# axiom_beta_sensor_cmv12000_tht_v0_16_r1_.net
KiCad netlist of a schematic drawn in EAGLE
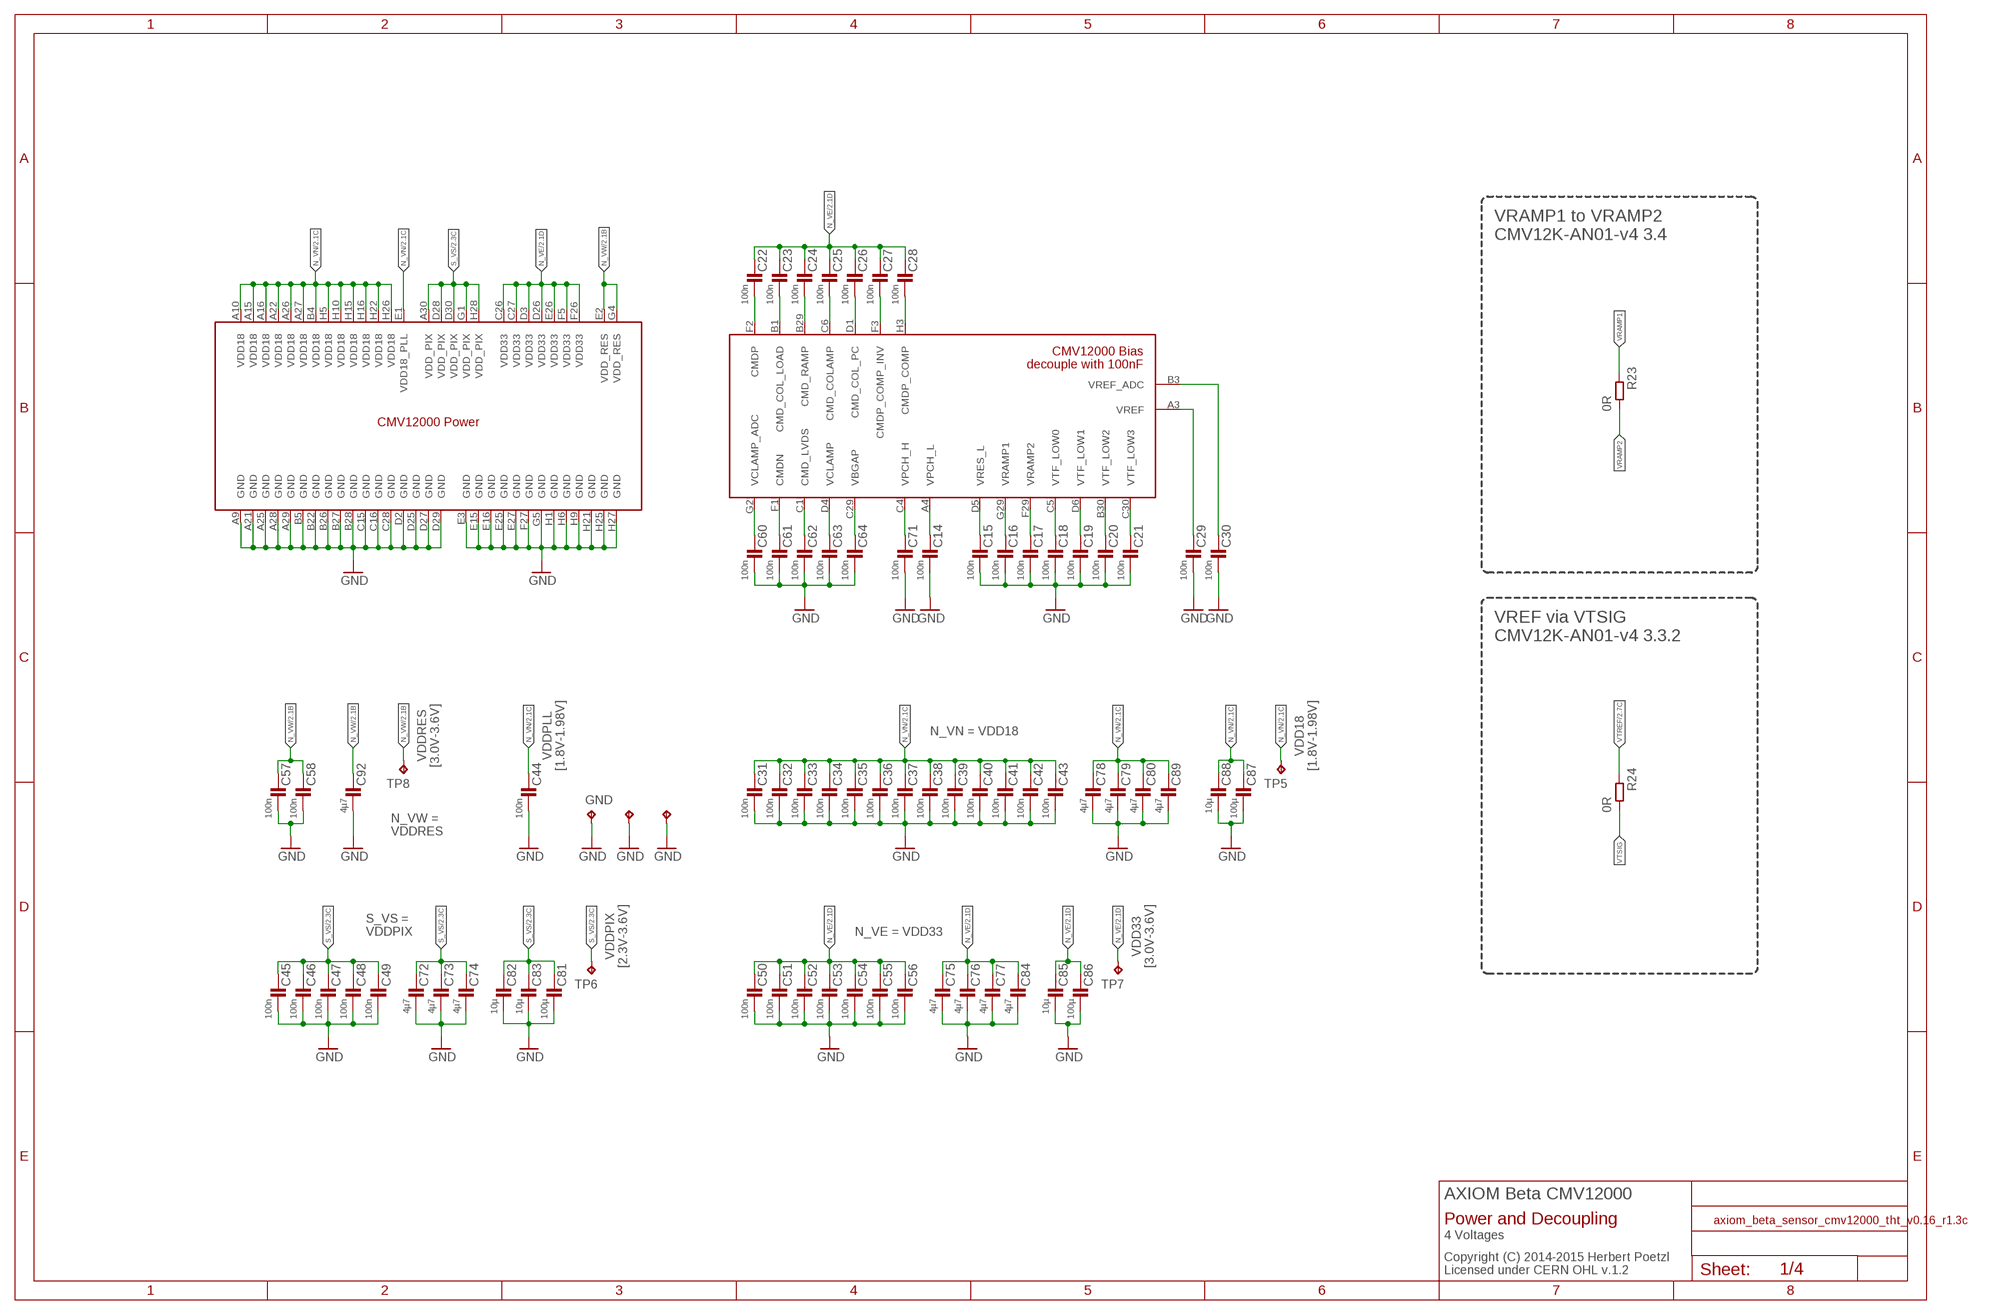
[diagram p0: schematic, sheet 1]
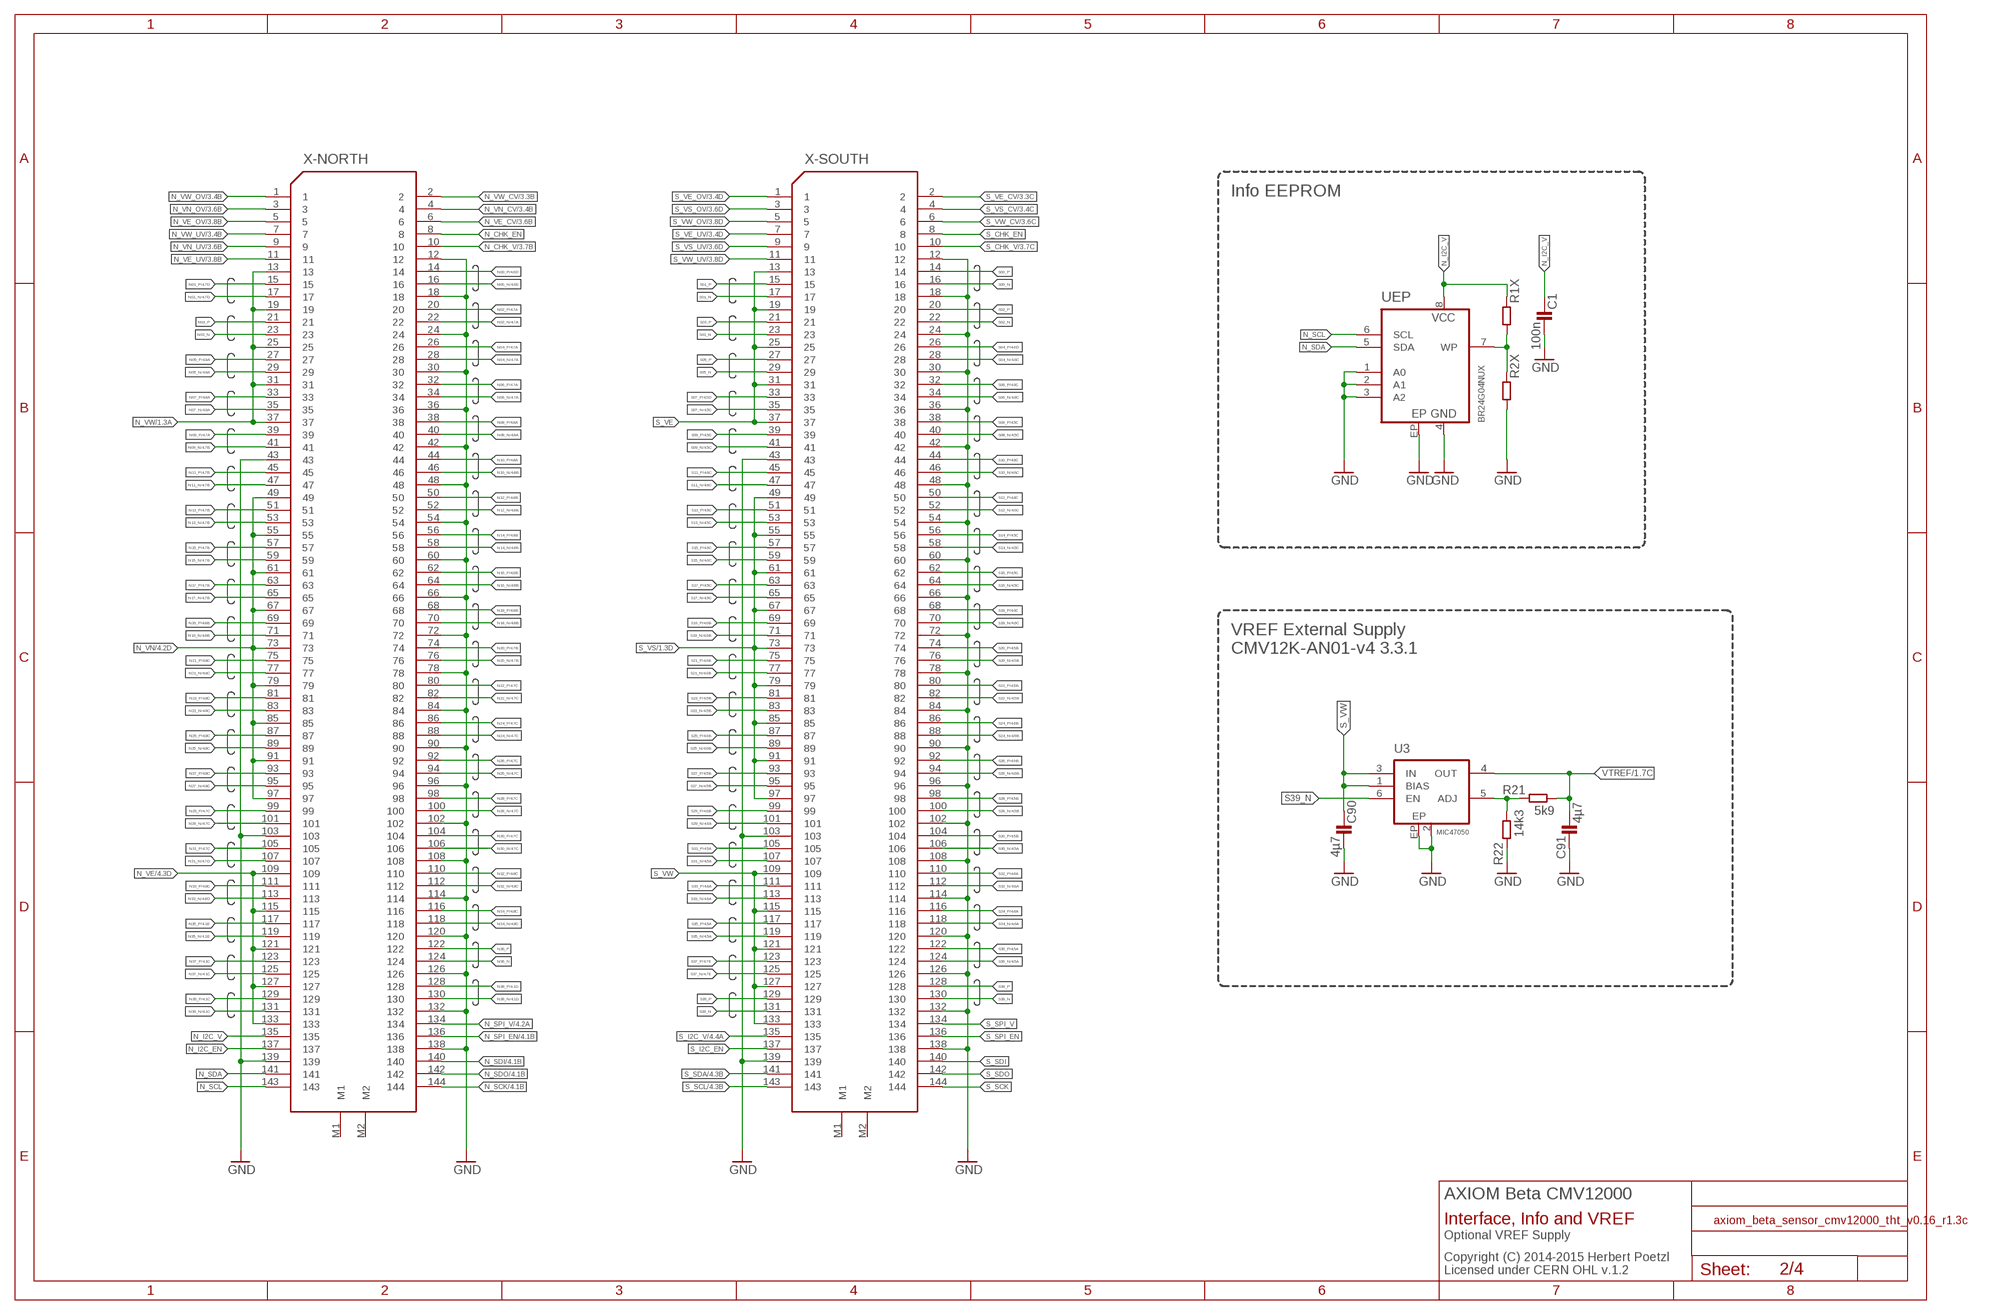
[diagram p1: schematic, sheet 2]
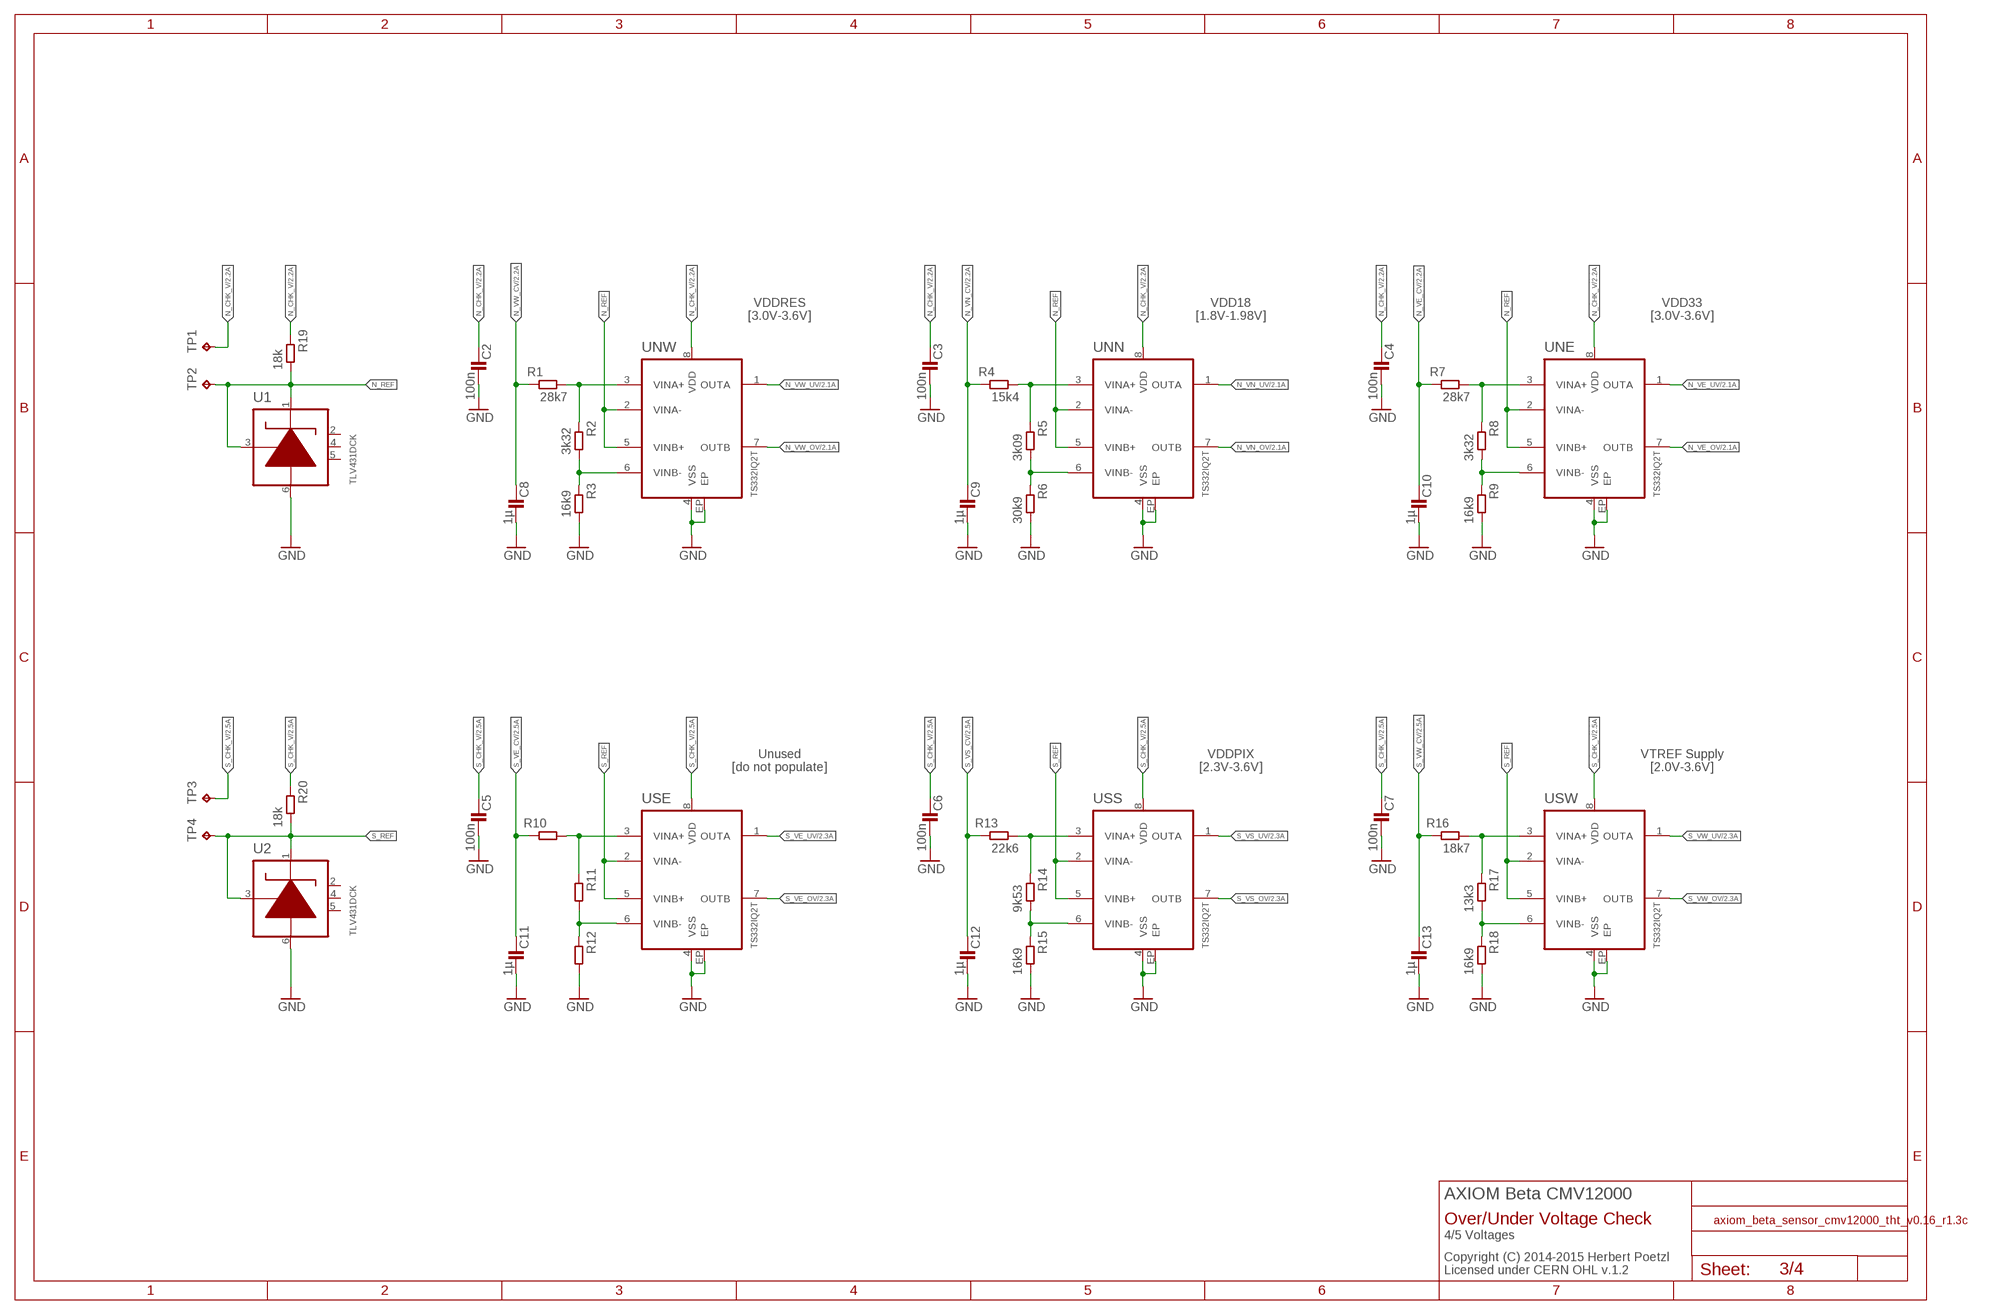
[diagram p2: schematic, sheet 3]
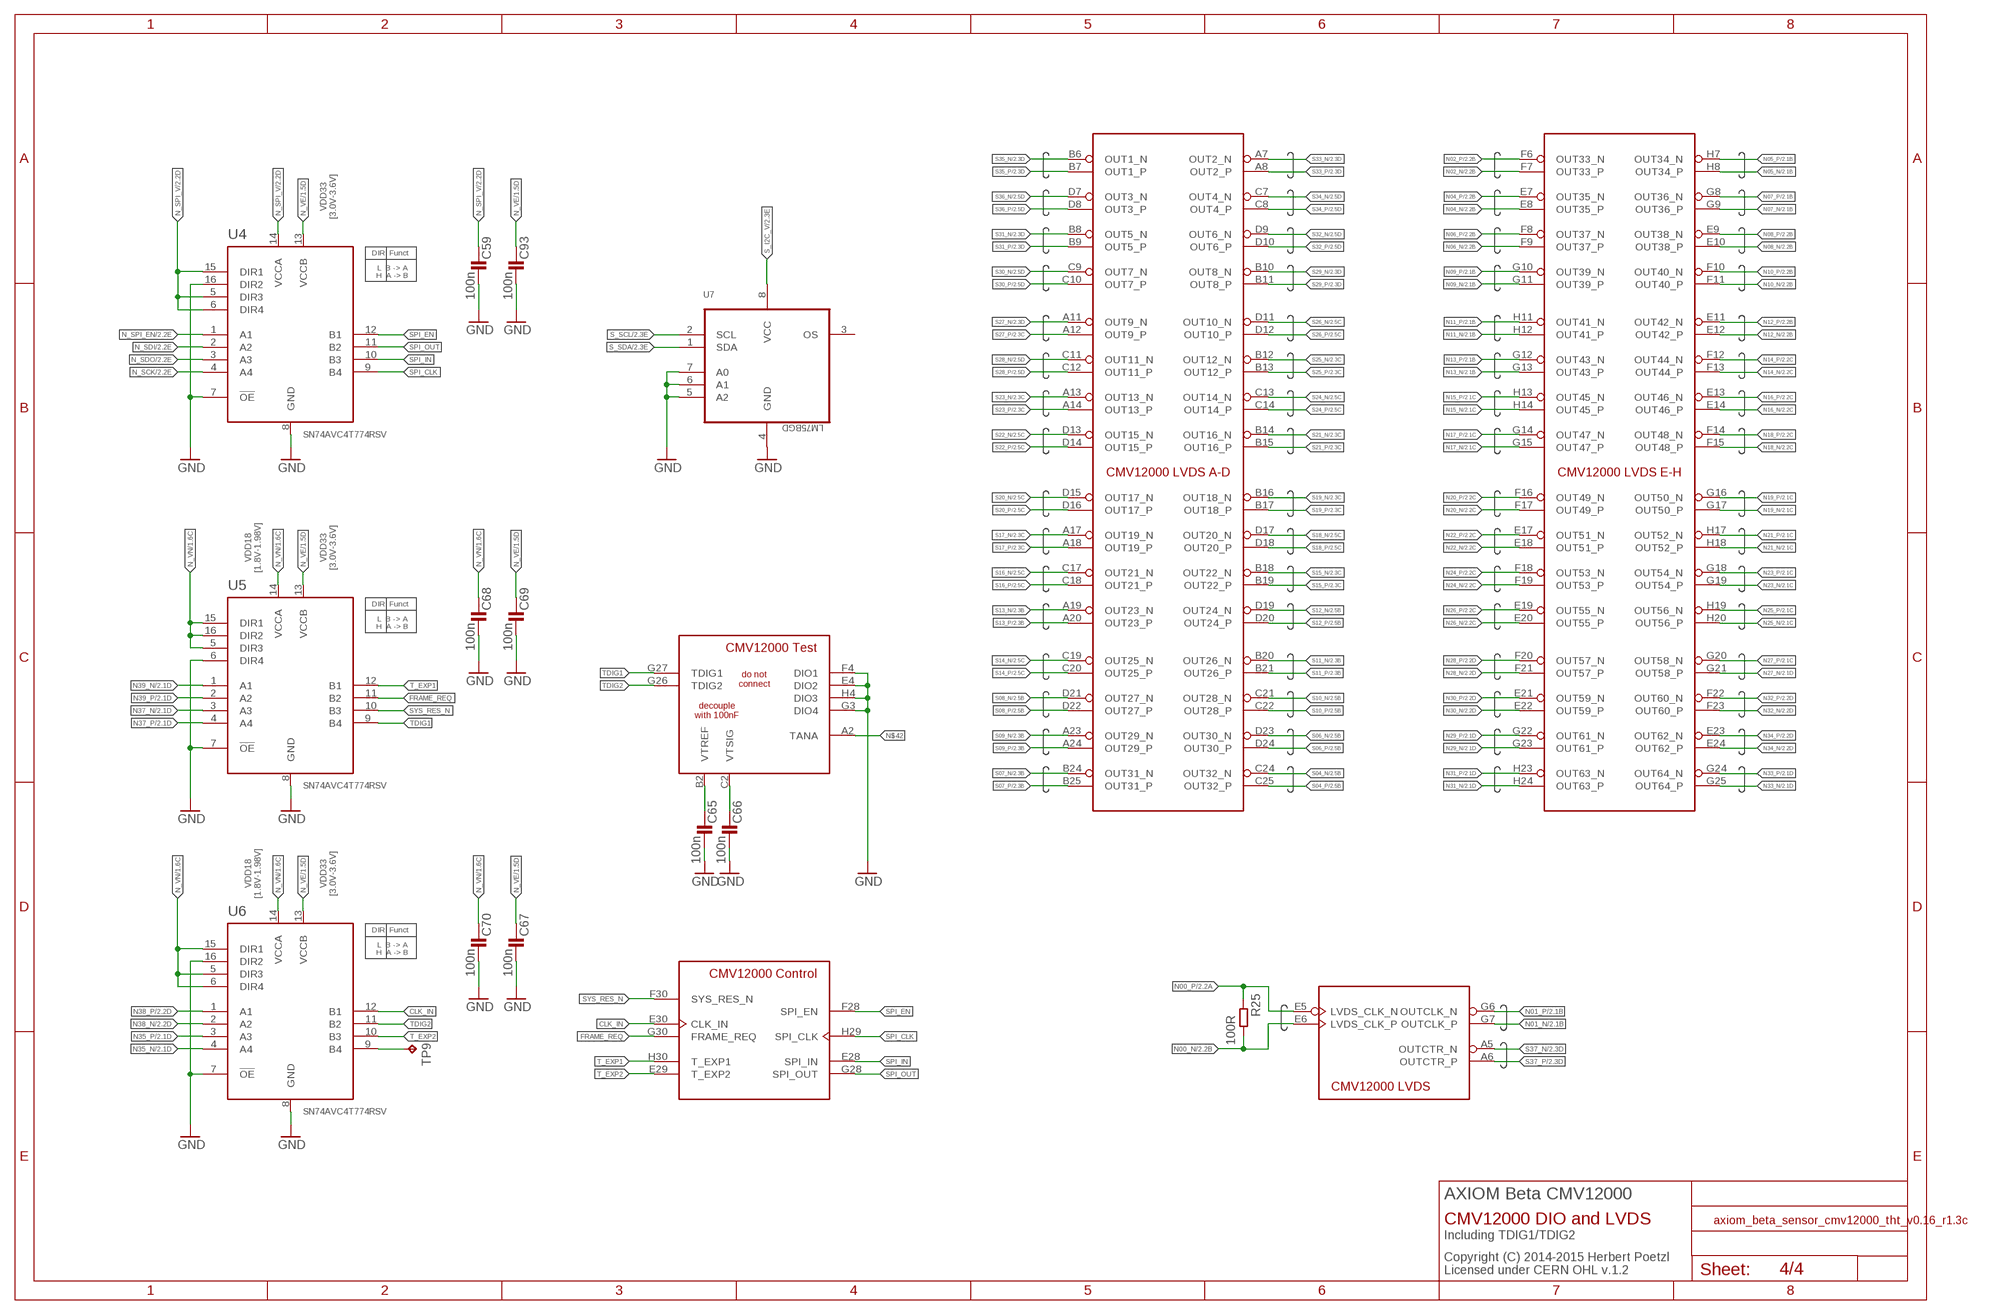
[diagram p3: schematic, sheet 4]

(export (version "E")
  (design (tool "Eeschema 10.0.6"))
  (components
    (comp (ref "C59")
      (value "100n")
      (footprint "eagle-import:0402-C")
      (libsource (lib "eagle-import") (part "C0402-C"))
    )
    (comp (ref "C65")
      (value "100n")
      (footprint "eagle-import:0402-C")
      (libsource (lib "eagle-import") (part "C0402-C"))
    )
    (comp (ref "C66")
      (value "100n")
      (footprint "eagle-import:0402-C")
      (libsource (lib "eagle-import") (part "C0402-C"))
    )
    (comp (ref "C67")
      (value "100n")
      (footprint "eagle-import:0402-C")
      (libsource (lib "eagle-import") (part "C0402-C"))
    )
    (comp (ref "C68")
      (value "100n")
      (footprint "eagle-import:0402-C")
      (libsource (lib "eagle-import") (part "C0402-C"))
    )
    (comp (ref "C69")
      (value "100n")
      (footprint "eagle-import:0402-C")
      (libsource (lib "eagle-import") (part "C0402-C"))
    )
    (comp (ref "C70")
      (value "100n")
      (footprint "eagle-import:0402-C")
      (libsource (lib "eagle-import") (part "C0402-C"))
    )
    (comp (ref "C93")
      (value "100n")
      (footprint "eagle-import:0402-C")
      (libsource (lib "eagle-import") (part "C0402-C"))
    )
    (comp (ref "R25")
      (value "100R")
      (footprint "eagle-import:0402-C")
      (libsource (lib "eagle-import") (part "R0402-C"))
    )
    (comp (ref "SENSOR")
      (value "CMV12000ANDON")
      (footprint "eagle-import:10-30-07-237-400T4")
      (libsource (lib "eagle-import") (part "CMV12000ANDON"))
    )
    (comp (ref "TP9")
      (value "TPTP10R")
      (footprint "eagle-import:TP10R")
      (libsource (lib "eagle-import") (part "TPTP10R"))
    )
    (comp (ref "U4")
      (value "SN74AVC4T774RSV")
      (footprint "eagle-import:QFN40P185X265X55-16N")
      (libsource (lib "eagle-import") (part "SN74AVC4T774RSV"))
    )
    (comp (ref "U5")
      (value "SN74AVC4T774RSV")
      (footprint "eagle-import:QFN40P185X265X55-16N")
      (libsource (lib "eagle-import") (part "SN74AVC4T774RSV"))
    )
    (comp (ref "U6")
      (value "SN74AVC4T774RSV")
      (footprint "eagle-import:QFN40P185X265X55-16N")
      (libsource (lib "eagle-import") (part "SN74AVC4T774RSV"))
    )
    (comp (ref "U7")
      (value "LM75BGD")
      (footprint "eagle-import:SOT996-2_3")
      (libsource (lib "eagle-import") (part "LM75BGD"))
    )
    (comp (ref "C2")
      (value "100n")
      (footprint "eagle-import:0402-C")
      (libsource (lib "eagle-import") (part "C0402-C"))
    )
    (comp (ref "C3")
      (value "100n")
      (footprint "eagle-import:0402-C")
      (libsource (lib "eagle-import") (part "C0402-C"))
    )
    (comp (ref "C4")
      (value "100n")
      (footprint "eagle-import:0402-C")
      (libsource (lib "eagle-import") (part "C0402-C"))
    )
    (comp (ref "C5")
      (value "100n")
      (footprint "eagle-import:0402-C")
      (libsource (lib "eagle-import") (part "C0402-C"))
    )
    (comp (ref "C6")
      (value "100n")
      (footprint "eagle-import:0402-C")
      (libsource (lib "eagle-import") (part "C0402-C"))
    )
    (comp (ref "C7")
      (value "100n")
      (footprint "eagle-import:0402-C")
      (libsource (lib "eagle-import") (part "C0402-C"))
    )
    (comp (ref "C8")
      (value "1µ")
      (footprint "eagle-import:0402-C")
      (libsource (lib "eagle-import") (part "C0402-C"))
    )
    (comp (ref "C9")
      (value "1µ")
      (footprint "eagle-import:0402-C")
      (libsource (lib "eagle-import") (part "C0402-C"))
    )
    (comp (ref "C10")
      (value "1µ")
      (footprint "eagle-import:0402-C")
      (libsource (lib "eagle-import") (part "C0402-C"))
    )
    (comp (ref "C11")
      (value "1µ")
      (footprint "eagle-import:0402-C")
      (libsource (lib "eagle-import") (part "C0402-C"))
    )
    (comp (ref "C12")
      (value "1µ")
      (footprint "eagle-import:0402-C")
      (libsource (lib "eagle-import") (part "C0402-C"))
    )
    (comp (ref "C13")
      (value "1µ")
      (footprint "eagle-import:0402-C")
      (libsource (lib "eagle-import") (part "C0402-C"))
    )
    (comp (ref "R1")
      (value "28k7")
      (footprint "eagle-import:0402-C")
      (libsource (lib "eagle-import") (part "R0402-C"))
    )
    (comp (ref "R2")
      (value "3k32")
      (footprint "eagle-import:0402-C")
      (libsource (lib "eagle-import") (part "R0402-C"))
    )
    (comp (ref "R3")
      (value "16k9")
      (footprint "eagle-import:0402-C")
      (libsource (lib "eagle-import") (part "R0402-C"))
    )
    (comp (ref "R4")
      (value "15k4")
      (footprint "eagle-import:0402-C")
      (libsource (lib "eagle-import") (part "R0402-C"))
    )
    (comp (ref "R5")
      (value "3k09")
      (footprint "eagle-import:0402-C")
      (libsource (lib "eagle-import") (part "R0402-C"))
    )
    (comp (ref "R6")
      (value "30k9")
      (footprint "eagle-import:0402-C")
      (libsource (lib "eagle-import") (part "R0402-C"))
    )
    (comp (ref "R7")
      (value "28k7")
      (footprint "eagle-import:0402-C")
      (libsource (lib "eagle-import") (part "R0402-C"))
    )
    (comp (ref "R8")
      (value "3k32")
      (footprint "eagle-import:0402-C")
      (libsource (lib "eagle-import") (part "R0402-C"))
    )
    (comp (ref "R9")
      (value "16k9")
      (footprint "eagle-import:0402-C")
      (libsource (lib "eagle-import") (part "R0402-C"))
    )
    (comp (ref "R10")
      (value "R0402-C")
      (footprint "eagle-import:0402-C")
      (libsource (lib "eagle-import") (part "R0402-C"))
    )
    (comp (ref "R11")
      (value "R0402-C")
      (footprint "eagle-import:0402-C")
      (libsource (lib "eagle-import") (part "R0402-C"))
    )
    (comp (ref "R12")
      (value "R0402-C")
      (footprint "eagle-import:0402-C")
      (libsource (lib "eagle-import") (part "R0402-C"))
    )
    (comp (ref "R13")
      (value "22k6")
      (footprint "eagle-import:0402-C")
      (libsource (lib "eagle-import") (part "R0402-C"))
    )
    (comp (ref "R14")
      (value "9k53")
      (footprint "eagle-import:0402-C")
      (libsource (lib "eagle-import") (part "R0402-C"))
    )
    (comp (ref "R15")
      (value "16k9")
      (footprint "eagle-import:0402-C")
      (libsource (lib "eagle-import") (part "R0402-C"))
    )
    (comp (ref "R16")
      (value "18k7")
      (footprint "eagle-import:0402-C")
      (libsource (lib "eagle-import") (part "R0402-C"))
    )
    (comp (ref "R17")
      (value "13k3")
      (footprint "eagle-import:0402-C")
      (libsource (lib "eagle-import") (part "R0402-C"))
    )
    (comp (ref "R18")
      (value "16k9")
      (footprint "eagle-import:0402-C")
      (libsource (lib "eagle-import") (part "R0402-C"))
    )
    (comp (ref "R19")
      (value "18k")
      (footprint "eagle-import:0402-C")
      (libsource (lib "eagle-import") (part "R0402-C"))
    )
    (comp (ref "R20")
      (value "18k")
      (footprint "eagle-import:0402-C")
      (libsource (lib "eagle-import") (part "R0402-C"))
    )
    (comp (ref "TP1")
      (value "TPTP10R")
      (footprint "eagle-import:TP10R")
      (libsource (lib "eagle-import") (part "TPTP10R"))
    )
    (comp (ref "TP2")
      (value "TPTP10R")
      (footprint "eagle-import:TP10R")
      (libsource (lib "eagle-import") (part "TPTP10R"))
    )
    (comp (ref "TP3")
      (value "TPTP10R")
      (footprint "eagle-import:TP10R")
      (libsource (lib "eagle-import") (part "TPTP10R"))
    )
    (comp (ref "TP4")
      (value "TPTP10R")
      (footprint "eagle-import:TP10R")
      (libsource (lib "eagle-import") (part "TPTP10R"))
    )
    (comp (ref "U1")
      (value "TLV431DCK")
      (footprint "eagle-import:SOT65P210X110-6N")
      (libsource (lib "eagle-import") (part "TLV431DCK"))
    )
    (comp (ref "U2")
      (value "TLV431DCK")
      (footprint "eagle-import:SOT65P210X110-6N")
      (libsource (lib "eagle-import") (part "TLV431DCK"))
    )
    (comp (ref "UNE")
      (value "TS332IQ2T")
      (footprint "eagle-import:DFN200X200X100-9N")
      (libsource (lib "eagle-import") (part "TS332IQ2T"))
    )
    (comp (ref "UNN")
      (value "TS332IQ2T")
      (footprint "eagle-import:DFN200X200X100-9N")
      (libsource (lib "eagle-import") (part "TS332IQ2T"))
    )
    (comp (ref "UNW")
      (value "TS332IQ2T")
      (footprint "eagle-import:DFN200X200X100-9N")
      (libsource (lib "eagle-import") (part "TS332IQ2T"))
    )
    (comp (ref "USE")
      (value "TS332IQ2T")
      (footprint "eagle-import:DFN200X200X100-9N")
      (libsource (lib "eagle-import") (part "TS332IQ2T"))
    )
    (comp (ref "USS")
      (value "TS332IQ2T")
      (footprint "eagle-import:DFN200X200X100-9N")
      (libsource (lib "eagle-import") (part "TS332IQ2T"))
    )
    (comp (ref "USW")
      (value "TS332IQ2T")
      (footprint "eagle-import:DFN200X200X100-9N")
      (libsource (lib "eagle-import") (part "TS332IQ2T"))
    )
    (comp (ref "C14")
      (value "100n")
      (footprint "eagle-import:0402-C")
      (libsource (lib "eagle-import") (part "C0402-C"))
    )
    (comp (ref "C15")
      (value "100n")
      (footprint "eagle-import:0402-C")
      (libsource (lib "eagle-import") (part "C0402-C"))
    )
    (comp (ref "C16")
      (value "100n")
      (footprint "eagle-import:0402-C")
      (libsource (lib "eagle-import") (part "C0402-C"))
    )
    (comp (ref "C17")
      (value "100n")
      (footprint "eagle-import:0402-C")
      (libsource (lib "eagle-import") (part "C0402-C"))
    )
    (comp (ref "C18")
      (value "100n")
      (footprint "eagle-import:0402-C")
      (libsource (lib "eagle-import") (part "C0402-C"))
    )
    (comp (ref "C19")
      (value "100n")
      (footprint "eagle-import:0402-C")
      (libsource (lib "eagle-import") (part "C0402-C"))
    )
    (comp (ref "C20")
      (value "100n")
      (footprint "eagle-import:0402-C")
      (libsource (lib "eagle-import") (part "C0402-C"))
    )
    (comp (ref "C21")
      (value "100n")
      (footprint "eagle-import:0402-C")
      (libsource (lib "eagle-import") (part "C0402-C"))
    )
    (comp (ref "C22")
      (value "100n")
      (footprint "eagle-import:0402-C")
      (libsource (lib "eagle-import") (part "C0402-C"))
    )
    (comp (ref "C23")
      (value "100n")
      (footprint "eagle-import:0402-C")
      (libsource (lib "eagle-import") (part "C0402-C"))
    )
    (comp (ref "C24")
      (value "100n")
      (footprint "eagle-import:0402-C")
      (libsource (lib "eagle-import") (part "C0402-C"))
    )
    (comp (ref "C25")
      (value "100n")
      (footprint "eagle-import:0402-C")
      (libsource (lib "eagle-import") (part "C0402-C"))
    )
    (comp (ref "C26")
      (value "100n")
      (footprint "eagle-import:0402-C")
      (libsource (lib "eagle-import") (part "C0402-C"))
    )
    (comp (ref "C27")
      (value "100n")
      (footprint "eagle-import:0402-C")
      (libsource (lib "eagle-import") (part "C0402-C"))
    )
    (comp (ref "C28")
      (value "100n")
      (footprint "eagle-import:0402-C")
      (libsource (lib "eagle-import") (part "C0402-C"))
    )
    (comp (ref "C29")
      (value "100n")
      (footprint "eagle-import:0402-C")
      (libsource (lib "eagle-import") (part "C0402-C"))
    )
    (comp (ref "C30")
      (value "100n")
      (footprint "eagle-import:0402-C")
      (libsource (lib "eagle-import") (part "C0402-C"))
    )
    (comp (ref "C31")
      (value "100n")
      (footprint "eagle-import:0402-C")
      (libsource (lib "eagle-import") (part "C0402-C"))
    )
    (comp (ref "C32")
      (value "100n")
      (footprint "eagle-import:0402-C")
      (libsource (lib "eagle-import") (part "C0402-C"))
    )
    (comp (ref "C33")
      (value "100n")
      (footprint "eagle-import:0402-C")
      (libsource (lib "eagle-import") (part "C0402-C"))
    )
    (comp (ref "C34")
      (value "100n")
      (footprint "eagle-import:0402-C")
      (libsource (lib "eagle-import") (part "C0402-C"))
    )
    (comp (ref "C35")
      (value "100n")
      (footprint "eagle-import:0402-C")
      (libsource (lib "eagle-import") (part "C0402-C"))
    )
    (comp (ref "C36")
      (value "100n")
      (footprint "eagle-import:0402-C")
      (libsource (lib "eagle-import") (part "C0402-C"))
    )
    (comp (ref "C37")
      (value "100n")
      (footprint "eagle-import:0402-C")
      (libsource (lib "eagle-import") (part "C0402-C"))
    )
    (comp (ref "C38")
      (value "100n")
      (footprint "eagle-import:0402-C")
      (libsource (lib "eagle-import") (part "C0402-C"))
    )
    (comp (ref "C39")
      (value "100n")
      (footprint "eagle-import:0402-C")
      (libsource (lib "eagle-import") (part "C0402-C"))
    )
    (comp (ref "C40")
      (value "100n")
      (footprint "eagle-import:0402-C")
      (libsource (lib "eagle-import") (part "C0402-C"))
    )
    (comp (ref "C41")
      (value "100n")
      (footprint "eagle-import:0402-C")
      (libsource (lib "eagle-import") (part "C0402-C"))
    )
    (comp (ref "C42")
      (value "100n")
      (footprint "eagle-import:0402-C")
      (libsource (lib "eagle-import") (part "C0402-C"))
    )
    (comp (ref "C43")
      (value "100n")
      (footprint "eagle-import:0402-C")
      (libsource (lib "eagle-import") (part "C0402-C"))
    )
    (comp (ref "C44")
      (value "100n")
      (footprint "eagle-import:0402-C")
      (libsource (lib "eagle-import") (part "C0402-C"))
    )
    (comp (ref "C45")
      (value "100n")
      (footprint "eagle-import:0402-C")
      (libsource (lib "eagle-import") (part "C0402-C"))
    )
    (comp (ref "C46")
      (value "100n")
      (footprint "eagle-import:0402-C")
      (libsource (lib "eagle-import") (part "C0402-C"))
    )
    (comp (ref "C47")
      (value "100n")
      (footprint "eagle-import:0402-C")
      (libsource (lib "eagle-import") (part "C0402-C"))
    )
    (comp (ref "C48")
      (value "100n")
      (footprint "eagle-import:0402-C")
      (libsource (lib "eagle-import") (part "C0402-C"))
    )
    (comp (ref "C49")
      (value "100n")
      (footprint "eagle-import:0402-C")
      (libsource (lib "eagle-import") (part "C0402-C"))
    )
    (comp (ref "C50")
      (value "100n")
      (footprint "eagle-import:0402-C")
      (libsource (lib "eagle-import") (part "C0402-C"))
    )
    (comp (ref "C51")
      (value "100n")
      (footprint "eagle-import:0402-C")
      (libsource (lib "eagle-import") (part "C0402-C"))
    )
    (comp (ref "C52")
      (value "100n")
      (footprint "eagle-import:0402-C")
      (libsource (lib "eagle-import") (part "C0402-C"))
    )
    (comp (ref "C53")
      (value "100n")
      (footprint "eagle-import:0402-C")
      (libsource (lib "eagle-import") (part "C0402-C"))
    )
    (comp (ref "C54")
      (value "100n")
      (footprint "eagle-import:0402-C")
      (libsource (lib "eagle-import") (part "C0402-C"))
    )
    (comp (ref "C55")
      (value "100n")
      (footprint "eagle-import:0402-C")
      (libsource (lib "eagle-import") (part "C0402-C"))
    )
    (comp (ref "C56")
      (value "100n")
      (footprint "eagle-import:0402-C")
      (libsource (lib "eagle-import") (part "C0402-C"))
    )
    (comp (ref "C57")
      (value "100n")
      (footprint "eagle-import:0402-C")
      (libsource (lib "eagle-import") (part "C0402-C"))
    )
    (comp (ref "C58")
      (value "100n")
      (footprint "eagle-import:0402-C")
      (libsource (lib "eagle-import") (part "C0402-C"))
    )
    (comp (ref "C60")
      (value "100n")
      (footprint "eagle-import:0402-C")
      (libsource (lib "eagle-import") (part "C0402-C"))
    )
    (comp (ref "C61")
      (value "100n")
      (footprint "eagle-import:0402-C")
      (libsource (lib "eagle-import") (part "C0402-C"))
    )
    (comp (ref "C62")
      (value "100n")
      (footprint "eagle-import:0402-C")
      (libsource (lib "eagle-import") (part "C0402-C"))
    )
    (comp (ref "C63")
      (value "100n")
      (footprint "eagle-import:0402-C")
      (libsource (lib "eagle-import") (part "C0402-C"))
    )
    (comp (ref "C64")
      (value "100n")
      (footprint "eagle-import:0402-C")
      (libsource (lib "eagle-import") (part "C0402-C"))
    )
    (comp (ref "C71")
      (value "100n")
      (footprint "eagle-import:0402-C")
      (libsource (lib "eagle-import") (part "C0402-C"))
    )
    (comp (ref "C72")
      (value "4µ7")
      (footprint "eagle-import:0402-B")
      (libsource (lib "eagle-import") (part "C0402-B"))
    )
    (comp (ref "C73")
      (value "4µ7")
      (footprint "eagle-import:0402-C")
      (libsource (lib "eagle-import") (part "C0402-C"))
    )
    (comp (ref "C74")
      (value "4µ7")
      (footprint "eagle-import:0402-C")
      (libsource (lib "eagle-import") (part "C0402-C"))
    )
    (comp (ref "C75")
      (value "4µ7")
      (footprint "eagle-import:0402-C")
      (libsource (lib "eagle-import") (part "C0402-C"))
    )
    (comp (ref "C76")
      (value "4µ7")
      (footprint "eagle-import:0402-C")
      (libsource (lib "eagle-import") (part "C0402-C"))
    )
    (comp (ref "C77")
      (value "4µ7")
      (footprint "eagle-import:0402-B")
      (libsource (lib "eagle-import") (part "C0402-B"))
    )
    (comp (ref "C78")
      (value "4µ7")
      (footprint "eagle-import:0402-B")
      (libsource (lib "eagle-import") (part "C0402-B"))
    )
    (comp (ref "C79")
      (value "4µ7")
      (footprint "eagle-import:0402-C")
      (libsource (lib "eagle-import") (part "C0402-C"))
    )
    (comp (ref "C80")
      (value "4µ7")
      (footprint "eagle-import:0402-C")
      (libsource (lib "eagle-import") (part "C0402-C"))
    )
    (comp (ref "C81")
      (value "100µ")
      (footprint "eagle-import:1206-B")
      (libsource (lib "eagle-import") (part "C1206-B"))
    )
    (comp (ref "C82")
      (value "10µ")
      (footprint "eagle-import:0603-C")
      (libsource (lib "eagle-import") (part "C0603-C"))
    )
    (comp (ref "C83")
      (value "10µ")
      (footprint "eagle-import:0603-C")
      (libsource (lib "eagle-import") (part "C0603-C"))
    )
    (comp (ref "C84")
      (value "4µ7")
      (footprint "eagle-import:0402-C")
      (libsource (lib "eagle-import") (part "C0402-C"))
    )
    (comp (ref "C85")
      (value "10µ")
      (footprint "eagle-import:0603-C")
      (libsource (lib "eagle-import") (part "C0603-C"))
    )
    (comp (ref "C86")
      (value "100µ")
      (footprint "eagle-import:1206-B")
      (libsource (lib "eagle-import") (part "C1206-B"))
    )
    (comp (ref "C87")
      (value "100µ")
      (footprint "eagle-import:1206-B")
      (libsource (lib "eagle-import") (part "C1206-B"))
    )
    (comp (ref "C88")
      (value "10µ")
      (footprint "eagle-import:0603-C")
      (libsource (lib "eagle-import") (part "C0603-C"))
    )
    (comp (ref "C89")
      (value "4µ7")
      (footprint "eagle-import:0402-C")
      (libsource (lib "eagle-import") (part "C0402-C"))
    )
    (comp (ref "C92")
      (value "4µ7")
      (footprint "eagle-import:0402-C")
      (libsource (lib "eagle-import") (part "C0402-C"))
    )
    (comp (ref "GND")
      (value "TPTP10R")
      (footprint "eagle-import:TP10R")
      (libsource (lib "eagle-import") (part "TPTP10R"))
    )
    (comp (ref "GND75")
      (value "TPTP10R")
      (footprint "eagle-import:TP10R")
      (libsource (lib "eagle-import") (part "TPTP10R"))
    )
    (comp (ref "GND77")
      (value "TPTP10R")
      (footprint "eagle-import:TP10R")
      (libsource (lib "eagle-import") (part "TPTP10R"))
    )
    (comp (ref "R23")
      (value "0R")
      (footprint "eagle-import:0402-C")
      (libsource (lib "eagle-import") (part "R0402-C"))
    )
    (comp (ref "R24")
      (value "0R")
      (footprint "eagle-import:0402-C")
      (libsource (lib "eagle-import") (part "R0402-C"))
    )
    (comp (ref "TP5")
      (value "TPTP10R")
      (footprint "eagle-import:TP10R")
      (libsource (lib "eagle-import") (part "TPTP10R"))
    )
    (comp (ref "TP6")
      (value "TPTP10R")
      (footprint "eagle-import:TP10R")
      (libsource (lib "eagle-import") (part "TPTP10R"))
    )
    (comp (ref "TP7")
      (value "TPTP10R")
      (footprint "eagle-import:TP10R")
      (libsource (lib "eagle-import") (part "TPTP10R"))
    )
    (comp (ref "TP8")
      (value "TPTP10R")
      (footprint "eagle-import:TP10R")
      (libsource (lib "eagle-import") (part "TPTP10R"))
    )
    (comp (ref "C1")
      (value "100n")
      (footprint "eagle-import:0402-C")
      (libsource (lib "eagle-import") (part "C0402-C"))
    )
    (comp (ref "C90")
      (value "4µ7")
      (footprint "eagle-import:0402-C")
      (libsource (lib "eagle-import") (part "C0402-C"))
    )
    (comp (ref "C91")
      (value "4µ7")
      (footprint "eagle-import:0402-C")
      (libsource (lib "eagle-import") (part "C0402-C"))
    )
    (comp (ref "R1X")
      (value "R0402-C")
      (footprint "eagle-import:0402-C")
      (libsource (lib "eagle-import") (part "R0402-C"))
    )
    (comp (ref "R2X")
      (value "R0402-C")
      (footprint "eagle-import:0402-C")
      (libsource (lib "eagle-import") (part "R0402-C"))
    )
    (comp (ref "R21")
      (value "5k9")
      (footprint "eagle-import:0402-C")
      (libsource (lib "eagle-import") (part "R0402-C"))
    )
    (comp (ref "R22")
      (value "14k3")
      (footprint "eagle-import:0402-C")
      (libsource (lib "eagle-import") (part "R0402-C"))
    )
    (comp (ref "U3")
      (value "MIC47050")
      (footprint "eagle-import:MLF-6")
      (libsource (lib "eagle-import") (part "MIC47050-ADJ"))
    )
    (comp (ref "UEP")
      (value "BR24G04NUX")
      (footprint "eagle-import:DFN200X300X100-9N")
      (libsource (lib "eagle-import") (part "BR24G04NUX"))
    )
    (comp (ref "X-NORTH")
      (value "FX10-144P")
      (footprint "eagle-import:FX10A-144P")
      (libsource (lib "eagle-import") (part "FX10-144P"))
    )
    (comp (ref "X-SOUTH")
      (value "FX10-144P")
      (footprint "eagle-import:FX10A-144P")
      (libsource (lib "eagle-import") (part "FX10-144P"))
    )
  )
  (nets
    (net (code "1") (name "CLK_IN") (class "Default")
      (node (ref "SENSOR") (pin "E30") (pinfunction "CLK_IN_E30") (pintype "input"))
      (node (ref "U6") (pin "12") (pinfunction "B1_12") (pintype "bidirectional"))
    )
    (net (code "2") (name "FRAME_REQ") (class "Default")
      (node (ref "SENSOR") (pin "G30") (pinfunction "FRAME_REQ_G30") (pintype "input"))
      (node (ref "U5") (pin "11") (pinfunction "B2_11") (pintype "bidirectional"))
    )
    (net (code "3") (name "GND") (class "Default")
      (node (ref "C1") (pin "2") (pinfunction "2_2") (pintype "passive"))
      (node (ref "C10") (pin "2") (pinfunction "2_2") (pintype "passive"))
      (node (ref "C11") (pin "2") (pinfunction "2_2") (pintype "passive"))
      (node (ref "C12") (pin "2") (pinfunction "2_2") (pintype "passive"))
      (node (ref "C13") (pin "2") (pinfunction "2_2") (pintype "passive"))
      (node (ref "C14") (pin "2") (pinfunction "2_2") (pintype "passive"))
      (node (ref "C15") (pin "2") (pinfunction "2_2") (pintype "passive"))
      (node (ref "C16") (pin "2") (pinfunction "2_2") (pintype "passive"))
      (node (ref "C17") (pin "2") (pinfunction "2_2") (pintype "passive"))
      (node (ref "C18") (pin "2") (pinfunction "2_2") (pintype "passive"))
      (node (ref "C19") (pin "2") (pinfunction "2_2") (pintype "passive"))
      (node (ref "C2") (pin "2") (pinfunction "2_2") (pintype "passive"))
      (node (ref "C20") (pin "2") (pinfunction "2_2") (pintype "passive"))
      (node (ref "C21") (pin "2") (pinfunction "2_2") (pintype "passive"))
      (node (ref "C29") (pin "2") (pinfunction "2_2") (pintype "passive"))
      (node (ref "C3") (pin "2") (pinfunction "2_2") (pintype "passive"))
      (node (ref "C30") (pin "2") (pinfunction "2_2") (pintype "passive"))
      (node (ref "C31") (pin "2") (pinfunction "2_2") (pintype "passive"))
      (node (ref "C32") (pin "2") (pinfunction "2_2") (pintype "passive"))
      (node (ref "C33") (pin "2") (pinfunction "2_2") (pintype "passive"))
      (node (ref "C34") (pin "2") (pinfunction "2_2") (pintype "passive"))
      (node (ref "C35") (pin "2") (pinfunction "2_2") (pintype "passive"))
      (node (ref "C36") (pin "2") (pinfunction "2_2") (pintype "passive"))
      (node (ref "C37") (pin "2") (pinfunction "2_2") (pintype "passive"))
      (node (ref "C38") (pin "2") (pinfunction "2_2") (pintype "passive"))
      (node (ref "C39") (pin "2") (pinfunction "2_2") (pintype "passive"))
      (node (ref "C4") (pin "2") (pinfunction "2_2") (pintype "passive"))
      (node (ref "C40") (pin "2") (pinfunction "2_2") (pintype "passive"))
      (node (ref "C41") (pin "2") (pinfunction "2_2") (pintype "passive"))
      (node (ref "C42") (pin "2") (pinfunction "2_2") (pintype "passive"))
      (node (ref "C43") (pin "2") (pinfunction "2_2") (pintype "passive"))
      (node (ref "C44") (pin "2") (pinfunction "2_2") (pintype "passive"))
      (node (ref "C45") (pin "2") (pinfunction "2_2") (pintype "passive"))
      (node (ref "C46") (pin "2") (pinfunction "2_2") (pintype "passive"))
      (node (ref "C47") (pin "2") (pinfunction "2_2") (pintype "passive"))
      (node (ref "C48") (pin "2") (pinfunction "2_2") (pintype "passive"))
      (node (ref "C49") (pin "2") (pinfunction "2_2") (pintype "passive"))
      (node (ref "C5") (pin "2") (pinfunction "2_2") (pintype "passive"))
      (node (ref "C50") (pin "2") (pinfunction "2_2") (pintype "passive"))
      (node (ref "C51") (pin "2") (pinfunction "2_2") (pintype "passive"))
      (node (ref "C52") (pin "2") (pinfunction "2_2") (pintype "passive"))
      (node (ref "C53") (pin "2") (pinfunction "2_2") (pintype "passive"))
      (node (ref "C54") (pin "2") (pinfunction "2_2") (pintype "passive"))
      (node (ref "C55") (pin "2") (pinfunction "2_2") (pintype "passive"))
      (node (ref "C56") (pin "2") (pinfunction "2_2") (pintype "passive"))
      (node (ref "C57") (pin "2") (pinfunction "2_2") (pintype "passive"))
      (node (ref "C58") (pin "2") (pinfunction "2_2") (pintype "passive"))
      (node (ref "C59") (pin "2") (pinfunction "2_2") (pintype "passive"))
      (node (ref "C6") (pin "2") (pinfunction "2_2") (pintype "passive"))
      (node (ref "C60") (pin "2") (pinfunction "2_2") (pintype "passive"))
      (node (ref "C61") (pin "2") (pinfunction "2_2") (pintype "passive"))
      (node (ref "C62") (pin "2") (pinfunction "2_2") (pintype "passive"))
      (node (ref "C63") (pin "2") (pinfunction "2_2") (pintype "passive"))
      (node (ref "C64") (pin "2") (pinfunction "2_2") (pintype "passive"))
      (node (ref "C65") (pin "2") (pinfunction "2_2") (pintype "passive"))
      (node (ref "C66") (pin "2") (pinfunction "2_2") (pintype "passive"))
      (node (ref "C67") (pin "2") (pinfunction "2_2") (pintype "passive"))
      (node (ref "C68") (pin "2") (pinfunction "2_2") (pintype "passive"))
      (node (ref "C69") (pin "2") (pinfunction "2_2") (pintype "passive"))
      (node (ref "C7") (pin "2") (pinfunction "2_2") (pintype "passive"))
      (node (ref "C70") (pin "2") (pinfunction "2_2") (pintype "passive"))
      (node (ref "C71") (pin "2") (pinfunction "2_2") (pintype "passive"))
      (node (ref "C72") (pin "2") (pinfunction "2_2") (pintype "passive"))
      (node (ref "C73") (pin "2") (pinfunction "2_2") (pintype "passive"))
      (node (ref "C74") (pin "2") (pinfunction "2_2") (pintype "passive"))
      (node (ref "C75") (pin "2") (pinfunction "2_2") (pintype "passive"))
      (node (ref "C76") (pin "2") (pinfunction "2_2") (pintype "passive"))
      (node (ref "C77") (pin "2") (pinfunction "2_2") (pintype "passive"))
      (node (ref "C78") (pin "2") (pinfunction "2_2") (pintype "passive"))
      (node (ref "C79") (pin "2") (pinfunction "2_2") (pintype "passive"))
      (node (ref "C8") (pin "2") (pinfunction "2_2") (pintype "passive"))
      (node (ref "C80") (pin "2") (pinfunction "2_2") (pintype "passive"))
      (node (ref "C81") (pin "2") (pinfunction "2_2") (pintype "passive"))
      (node (ref "C82") (pin "2") (pinfunction "2_2") (pintype "passive"))
      (node (ref "C83") (pin "2") (pinfunction "2_2") (pintype "passive"))
      (node (ref "C84") (pin "2") (pinfunction "2_2") (pintype "passive"))
      (node (ref "C85") (pin "2") (pinfunction "2_2") (pintype "passive"))
      (node (ref "C86") (pin "2") (pinfunction "2_2") (pintype "passive"))
      (node (ref "C87") (pin "2") (pinfunction "2_2") (pintype "passive"))
      (node (ref "C88") (pin "2") (pinfunction "2_2") (pintype "passive"))
      (node (ref "C89") (pin "2") (pinfunction "2_2") (pintype "passive"))
      (node (ref "C9") (pin "2") (pinfunction "2_2") (pintype "passive"))
      (node (ref "C90") (pin "2") (pinfunction "2_2") (pintype "passive"))
      (node (ref "C91") (pin "1") (pinfunction "1_1") (pintype "passive"))
      (node (ref "C92") (pin "2") (pinfunction "2_2") (pintype "passive"))
      (node (ref "C93") (pin "2") (pinfunction "2_2") (pintype "passive"))
      (node (ref "GND") (pin "TP") (pinfunction "TP_TP") (pintype "input"))
      (node (ref "GND75") (pin "TP") (pinfunction "TP_TP") (pintype "input"))
      (node (ref "GND77") (pin "TP") (pinfunction "TP_TP") (pintype "input"))
      (node (ref "R12") (pin "2") (pinfunction "2_2") (pintype "passive"))
      (node (ref "R15") (pin "2") (pinfunction "2_2") (pintype "passive"))
      (node (ref "R18") (pin "2") (pinfunction "2_2") (pintype "passive"))
      (node (ref "R22") (pin "1") (pinfunction "1_1") (pintype "passive"))
      (node (ref "R2X") (pin "2") (pinfunction "2_2") (pintype "passive"))
      (node (ref "R3") (pin "2") (pinfunction "2_2") (pintype "passive"))
      (node (ref "R6") (pin "2") (pinfunction "2_2") (pintype "passive"))
      (node (ref "R9") (pin "2") (pinfunction "2_2") (pintype "passive"))
      (node (ref "SENSOR") (pin "A21") (pinfunction "GND_A21") (pintype "power_in"))
      (node (ref "SENSOR") (pin "A25") (pinfunction "GND_A25") (pintype "power_in"))
      (node (ref "SENSOR") (pin "A28") (pinfunction "GND_A28") (pintype "power_in"))
      (node (ref "SENSOR") (pin "A29") (pinfunction "GND_A29") (pintype "power_in"))
      (node (ref "SENSOR") (pin "A9") (pinfunction "GND_A9") (pintype "power_in"))
      (node (ref "SENSOR") (pin "B22") (pinfunction "GND_B22") (pintype "power_in"))
      (node (ref "SENSOR") (pin "B26") (pinfunction "GND_B26") (pintype "power_in"))
      (node (ref "SENSOR") (pin "B27") (pinfunction "GND_B27") (pintype "power_in"))
      (node (ref "SENSOR") (pin "B28") (pinfunction "GND_B28") (pintype "power_in"))
      (node (ref "SENSOR") (pin "B5") (pinfunction "GND_B5") (pintype "power_in"))
      (node (ref "SENSOR") (pin "C15") (pinfunction "GND_C15") (pintype "power_in"))
      (node (ref "SENSOR") (pin "C16") (pinfunction "GND_C16") (pintype "power_in"))
      (node (ref "SENSOR") (pin "C28") (pinfunction "GND_C28") (pintype "power_in"))
      (node (ref "SENSOR") (pin "D2") (pinfunction "GND_D2") (pintype "power_in"))
      (node (ref "SENSOR") (pin "D25") (pinfunction "GND_D25") (pintype "power_in"))
      (node (ref "SENSOR") (pin "D27") (pinfunction "GND_D27") (pintype "power_in"))
      (node (ref "SENSOR") (pin "D29") (pinfunction "GND_D29") (pintype "power_in"))
      (node (ref "SENSOR") (pin "E15") (pinfunction "GND_E15") (pintype "power_in"))
      (node (ref "SENSOR") (pin "E16") (pinfunction "GND_E16") (pintype "power_in"))
      (node (ref "SENSOR") (pin "E25") (pinfunction "GND_E25") (pintype "power_in"))
      (node (ref "SENSOR") (pin "E27") (pinfunction "GND_E27") (pintype "power_in"))
      (node (ref "SENSOR") (pin "E3") (pinfunction "GND_E3") (pintype "power_in"))
      (node (ref "SENSOR") (pin "E4") (pinfunction "DIO2_E4") (pintype "output"))
      (node (ref "SENSOR") (pin "F27") (pinfunction "GND_F27") (pintype "power_in"))
      (node (ref "SENSOR") (pin "F4") (pinfunction "DIO1_F4") (pintype "output"))
      (node (ref "SENSOR") (pin "G3") (pinfunction "DIO4_G3") (pintype "output"))
      (node (ref "SENSOR") (pin "G5") (pinfunction "GND_G5") (pintype "power_in"))
      (node (ref "SENSOR") (pin "H1") (pinfunction "GND_H1") (pintype "power_in"))
      (node (ref "SENSOR") (pin "H21") (pinfunction "GND_H21") (pintype "power_in"))
      (node (ref "SENSOR") (pin "H25") (pinfunction "GND_H25") (pintype "power_in"))
      (node (ref "SENSOR") (pin "H27") (pinfunction "GND_H27") (pintype "power_in"))
      (node (ref "SENSOR") (pin "H4") (pinfunction "DIO3_H4") (pintype "output"))
      (node (ref "SENSOR") (pin "H6") (pinfunction "GND_H6") (pintype "power_in"))
      (node (ref "SENSOR") (pin "H9") (pinfunction "GND_H9") (pintype "power_in"))
      (node (ref "U1") (pin "6") (pinfunction "ANODE_6") (pintype "input"))
      (node (ref "U2") (pin "6") (pinfunction "ANODE_6") (pintype "input"))
      (node (ref "U3") (pin "2") (pinfunction "GND_2") (pintype "power_in"))
      (node (ref "U3") (pin "EP") (pinfunction "EP_EP") (pintype "power_in"))
      (node (ref "U4") (pin "16") (pinfunction "DIR2_16") (pintype "input"))
      (node (ref "U4") (pin "7") (pinfunction "~{OE}_7") (pintype "input"))
      (node (ref "U4") (pin "8") (pinfunction "GND_8") (pintype "passive"))
      (node (ref "U5") (pin "6") (pinfunction "DIR4_6") (pintype "input"))
      (node (ref "U5") (pin "7") (pinfunction "~{OE}_7") (pintype "input"))
      (node (ref "U5") (pin "8") (pinfunction "GND_8") (pintype "passive"))
      (node (ref "U6") (pin "16") (pinfunction "DIR2_16") (pintype "input"))
      (node (ref "U6") (pin "7") (pinfunction "~{OE}_7") (pintype "input"))
      (node (ref "U6") (pin "8") (pinfunction "GND_8") (pintype "passive"))
      (node (ref "U7") (pin "4") (pinfunction "GND_4") (pintype "power_in"))
      (node (ref "U7") (pin "5") (pinfunction "A2_5") (pintype "input"))
      (node (ref "U7") (pin "6") (pinfunction "A1_6") (pintype "input"))
      (node (ref "U7") (pin "7") (pinfunction "A0_7") (pintype "input"))
      (node (ref "UEP") (pin "1") (pinfunction "A0_1") (pintype "input"))
      (node (ref "UEP") (pin "2") (pinfunction "A1_2") (pintype "input"))
      (node (ref "UEP") (pin "3") (pinfunction "A2_3") (pintype "input"))
      (node (ref "UEP") (pin "4") (pinfunction "GND_4") (pintype "passive"))
      (node (ref "UEP") (pin "EP") (pinfunction "EP_EP") (pintype "passive"))
      (node (ref "UNE") (pin "4") (pinfunction "VSS_4") (pintype "power_in"))
      (node (ref "UNE") (pin "EP") (pinfunction "EP_EP") (pintype "passive"))
      (node (ref "UNN") (pin "4") (pinfunction "VSS_4") (pintype "power_in"))
      (node (ref "UNN") (pin "EP") (pinfunction "EP_EP") (pintype "passive"))
      (node (ref "UNW") (pin "4") (pinfunction "VSS_4") (pintype "power_in"))
      (node (ref "UNW") (pin "EP") (pinfunction "EP_EP") (pintype "passive"))
      (node (ref "USE") (pin "4") (pinfunction "VSS_4") (pintype "power_in"))
      (node (ref "USE") (pin "EP") (pinfunction "EP_EP") (pintype "passive"))
      (node (ref "USS") (pin "4") (pinfunction "VSS_4") (pintype "power_in"))
      (node (ref "USS") (pin "EP") (pinfunction "EP_EP") (pintype "passive"))
      (node (ref "USW") (pin "4") (pinfunction "VSS_4") (pintype "power_in"))
      (node (ref "USW") (pin "EP") (pinfunction "EP_EP") (pintype "passive"))
      (node (ref "X-NORTH") (pin "102") (pinfunction "102_102") (pintype "bidirectional"))
      (node (ref "X-NORTH") (pin "103") (pinfunction "103_103") (pintype "bidirectional"))
      (node (ref "X-NORTH") (pin "108") (pinfunction "108_108") (pintype "bidirectional"))
      (node (ref "X-NORTH") (pin "114") (pinfunction "114_114") (pintype "bidirectional"))
      (node (ref "X-NORTH") (pin "12") (pinfunction "12_12") (pintype "bidirectional"))
      (node (ref "X-NORTH") (pin "120") (pinfunction "120_120") (pintype "bidirectional"))
      (node (ref "X-NORTH") (pin "126") (pinfunction "126_126") (pintype "bidirectional"))
      (node (ref "X-NORTH") (pin "132") (pinfunction "132_132") (pintype "bidirectional"))
      (node (ref "X-NORTH") (pin "138") (pinfunction "138_138") (pintype "bidirectional"))
      (node (ref "X-NORTH") (pin "139") (pinfunction "139_139") (pintype "bidirectional"))
      (node (ref "X-NORTH") (pin "18") (pinfunction "18_18") (pintype "bidirectional"))
      (node (ref "X-NORTH") (pin "24") (pinfunction "24_24") (pintype "bidirectional"))
      (node (ref "X-NORTH") (pin "30") (pinfunction "30_30") (pintype "bidirectional"))
      (node (ref "X-NORTH") (pin "36") (pinfunction "36_36") (pintype "bidirectional"))
      (node (ref "X-NORTH") (pin "42") (pinfunction "42_42") (pintype "bidirectional"))
      (node (ref "X-NORTH") (pin "43") (pinfunction "43_43") (pintype "bidirectional"))
      (node (ref "X-NORTH") (pin "48") (pinfunction "48_48") (pintype "bidirectional"))
      (node (ref "X-NORTH") (pin "54") (pinfunction "54_54") (pintype "bidirectional"))
      (node (ref "X-NORTH") (pin "60") (pinfunction "60_60") (pintype "bidirectional"))
      (node (ref "X-NORTH") (pin "66") (pinfunction "66_66") (pintype "bidirectional"))
      (node (ref "X-NORTH") (pin "72") (pinfunction "72_72") (pintype "bidirectional"))
      (node (ref "X-NORTH") (pin "78") (pinfunction "78_78") (pintype "bidirectional"))
      (node (ref "X-NORTH") (pin "84") (pinfunction "84_84") (pintype "bidirectional"))
      (node (ref "X-NORTH") (pin "90") (pinfunction "90_90") (pintype "bidirectional"))
      (node (ref "X-NORTH") (pin "96") (pinfunction "96_96") (pintype "bidirectional"))
      (node (ref "X-SOUTH") (pin "102") (pinfunction "102_102") (pintype "bidirectional"))
      (node (ref "X-SOUTH") (pin "103") (pinfunction "103_103") (pintype "bidirectional"))
      (node (ref "X-SOUTH") (pin "108") (pinfunction "108_108") (pintype "bidirectional"))
      (node (ref "X-SOUTH") (pin "114") (pinfunction "114_114") (pintype "bidirectional"))
      (node (ref "X-SOUTH") (pin "12") (pinfunction "12_12") (pintype "bidirectional"))
      (node (ref "X-SOUTH") (pin "120") (pinfunction "120_120") (pintype "bidirectional"))
      (node (ref "X-SOUTH") (pin "126") (pinfunction "126_126") (pintype "bidirectional"))
      (node (ref "X-SOUTH") (pin "132") (pinfunction "132_132") (pintype "bidirectional"))
      (node (ref "X-SOUTH") (pin "138") (pinfunction "138_138") (pintype "bidirectional"))
      (node (ref "X-SOUTH") (pin "139") (pinfunction "139_139") (pintype "bidirectional"))
      (node (ref "X-SOUTH") (pin "18") (pinfunction "18_18") (pintype "bidirectional"))
      (node (ref "X-SOUTH") (pin "24") (pinfunction "24_24") (pintype "bidirectional"))
      (node (ref "X-SOUTH") (pin "30") (pinfunction "30_30") (pintype "bidirectional"))
      (node (ref "X-SOUTH") (pin "36") (pinfunction "36_36") (pintype "bidirectional"))
      (node (ref "X-SOUTH") (pin "42") (pinfunction "42_42") (pintype "bidirectional"))
      (node (ref "X-SOUTH") (pin "43") (pinfunction "43_43") (pintype "bidirectional"))
      (node (ref "X-SOUTH") (pin "48") (pinfunction "48_48") (pintype "bidirectional"))
      (node (ref "X-SOUTH") (pin "54") (pinfunction "54_54") (pintype "bidirectional"))
      (node (ref "X-SOUTH") (pin "60") (pinfunction "60_60") (pintype "bidirectional"))
      (node (ref "X-SOUTH") (pin "66") (pinfunction "66_66") (pintype "bidirectional"))
      (node (ref "X-SOUTH") (pin "72") (pinfunction "72_72") (pintype "bidirectional"))
      (node (ref "X-SOUTH") (pin "78") (pinfunction "78_78") (pintype "bidirectional"))
      (node (ref "X-SOUTH") (pin "84") (pinfunction "84_84") (pintype "bidirectional"))
      (node (ref "X-SOUTH") (pin "90") (pinfunction "90_90") (pintype "bidirectional"))
      (node (ref "X-SOUTH") (pin "96") (pinfunction "96_96") (pintype "bidirectional"))
    )
    (net (code "4") (name "N$42") (class "Default")
      (node (ref "SENSOR") (pin "A2") (pinfunction "TANA_A2") (pintype "output"))
    )
    (net (code "5") (name "N00_N") (class "Default")
      (node (ref "R25") (pin "2") (pinfunction "2_2") (pintype "passive"))
      (node (ref "SENSOR") (pin "E6") (pinfunction "LVDS_CLK_P_E6") (pintype "input"))
      (node (ref "X-NORTH") (pin "16") (pinfunction "16_16") (pintype "bidirectional"))
    )
    (net (code "6") (name "N00_P") (class "Default")
      (node (ref "R25") (pin "1") (pinfunction "1_1") (pintype "passive"))
      (node (ref "SENSOR") (pin "E5") (pinfunction "LVDS_CLK_N_E5") (pintype "input"))
      (node (ref "X-NORTH") (pin "14") (pinfunction "14_14") (pintype "bidirectional"))
    )
    (net (code "7") (name "N01_N") (class "Default")
      (node (ref "SENSOR") (pin "G7") (pinfunction "OUTCLK_P_G7") (pintype "output"))
      (node (ref "X-NORTH") (pin "17") (pinfunction "17_17") (pintype "bidirectional"))
    )
    (net (code "8") (name "N01_P") (class "Default")
      (node (ref "SENSOR") (pin "G6") (pinfunction "OUTCLK_N_G6") (pintype "output"))
      (node (ref "X-NORTH") (pin "15") (pinfunction "15_15") (pintype "bidirectional"))
    )
    (net (code "9") (name "N02_N") (class "Default")
      (node (ref "SENSOR") (pin "F7") (pinfunction "OUT33_P_F7") (pintype "output"))
      (node (ref "X-NORTH") (pin "22") (pinfunction "22_22") (pintype "bidirectional"))
    )
    (net (code "10") (name "N02_P") (class "Default")
      (node (ref "SENSOR") (pin "F6") (pinfunction "OUT33_N_F6") (pintype "output"))
      (node (ref "X-NORTH") (pin "20") (pinfunction "20_20") (pintype "bidirectional"))
    )
    (net (code "11") (name "N03_N") (class "Default")
      (node (ref "X-NORTH") (pin "23") (pinfunction "23_23") (pintype "bidirectional"))
    )
    (net (code "12") (name "N03_P") (class "Default")
      (node (ref "X-NORTH") (pin "21") (pinfunction "21_21") (pintype "bidirectional"))
    )
    (net (code "13") (name "N04_N") (class "Default")
      (node (ref "SENSOR") (pin "E8") (pinfunction "OUT35_P_E8") (pintype "output"))
      (node (ref "X-NORTH") (pin "28") (pinfunction "28_28") (pintype "bidirectional"))
    )
    (net (code "14") (name "N04_P") (class "Default")
      (node (ref "SENSOR") (pin "E7") (pinfunction "OUT35_N_E7") (pintype "output"))
      (node (ref "X-NORTH") (pin "26") (pinfunction "26_26") (pintype "bidirectional"))
    )
    (net (code "15") (name "N05_N") (class "Default")
      (node (ref "SENSOR") (pin "H8") (pinfunction "OUT34_P_H8") (pintype "output"))
      (node (ref "X-NORTH") (pin "29") (pinfunction "29_29") (pintype "bidirectional"))
    )
    (net (code "16") (name "N05_P") (class "Default")
      (node (ref "SENSOR") (pin "H7") (pinfunction "OUT34_N_H7") (pintype "output"))
      (node (ref "X-NORTH") (pin "27") (pinfunction "27_27") (pintype "bidirectional"))
    )
    (net (code "17") (name "N06_N") (class "Default")
      (node (ref "SENSOR") (pin "F9") (pinfunction "OUT37_P_F9") (pintype "output"))
      (node (ref "X-NORTH") (pin "34") (pinfunction "34_34") (pintype "bidirectional"))
    )
    (net (code "18") (name "N06_P") (class "Default")
      (node (ref "SENSOR") (pin "F8") (pinfunction "OUT37_N_F8") (pintype "output"))
      (node (ref "X-NORTH") (pin "32") (pinfunction "32_32") (pintype "bidirectional"))
    )
    (net (code "19") (name "N07_N") (class "Default")
      (node (ref "SENSOR") (pin "G9") (pinfunction "OUT36_P_G9") (pintype "output"))
      (node (ref "X-NORTH") (pin "35") (pinfunction "35_35") (pintype "bidirectional"))
    )
    (net (code "20") (name "N07_P") (class "Default")
      (node (ref "SENSOR") (pin "G8") (pinfunction "OUT36_N_G8") (pintype "output"))
      (node (ref "X-NORTH") (pin "33") (pinfunction "33_33") (pintype "bidirectional"))
    )
    (net (code "21") (name "N08_N") (class "Default")
      (node (ref "SENSOR") (pin "E10") (pinfunction "OUT38_P_E10") (pintype "output"))
      (node (ref "X-NORTH") (pin "40") (pinfunction "40_40") (pintype "bidirectional"))
    )
    (net (code "22") (name "N08_P") (class "Default")
      (node (ref "SENSOR") (pin "E9") (pinfunction "OUT38_N_E9") (pintype "output"))
      (node (ref "X-NORTH") (pin "38") (pinfunction "38_38") (pintype "bidirectional"))
    )
    (net (code "23") (name "N09_N") (class "Default")
      (node (ref "SENSOR") (pin "G11") (pinfunction "OUT39_P_G11") (pintype "output"))
      (node (ref "X-NORTH") (pin "41") (pinfunction "41_41") (pintype "bidirectional"))
    )
    (net (code "24") (name "N09_P") (class "Default")
      (node (ref "SENSOR") (pin "G10") (pinfunction "OUT39_N_G10") (pintype "output"))
      (node (ref "X-NORTH") (pin "39") (pinfunction "39_39") (pintype "bidirectional"))
    )
    (net (code "25") (name "N10_N") (class "Default")
      (node (ref "SENSOR") (pin "F11") (pinfunction "OUT40_P_F11") (pintype "output"))
      (node (ref "X-NORTH") (pin "46") (pinfunction "46_46") (pintype "bidirectional"))
    )
    (net (code "26") (name "N10_P") (class "Default")
      (node (ref "SENSOR") (pin "F10") (pinfunction "OUT40_N_F10") (pintype "output"))
      (node (ref "X-NORTH") (pin "44") (pinfunction "44_44") (pintype "bidirectional"))
    )
    (net (code "27") (name "N11_N") (class "Default")
      (node (ref "SENSOR") (pin "H12") (pinfunction "OUT41_P_H12") (pintype "output"))
      (node (ref "X-NORTH") (pin "47") (pinfunction "47_47") (pintype "bidirectional"))
    )
    (net (code "28") (name "N11_P") (class "Default")
      (node (ref "SENSOR") (pin "H11") (pinfunction "OUT41_N_H11") (pintype "output"))
      (node (ref "X-NORTH") (pin "45") (pinfunction "45_45") (pintype "bidirectional"))
    )
    (net (code "29") (name "N12_N") (class "Default")
      (node (ref "SENSOR") (pin "E12") (pinfunction "OUT42_P_E12") (pintype "output"))
      (node (ref "X-NORTH") (pin "52") (pinfunction "52_52") (pintype "bidirectional"))
    )
    (net (code "30") (name "N12_P") (class "Default")
      (node (ref "SENSOR") (pin "E11") (pinfunction "OUT42_N_E11") (pintype "output"))
      (node (ref "X-NORTH") (pin "50") (pinfunction "50_50") (pintype "bidirectional"))
    )
    (net (code "31") (name "N13_N") (class "Default")
      (node (ref "SENSOR") (pin "G13") (pinfunction "OUT43_P_G13") (pintype "output"))
      (node (ref "X-NORTH") (pin "53") (pinfunction "53_53") (pintype "bidirectional"))
    )
    (net (code "32") (name "N13_P") (class "Default")
      (node (ref "SENSOR") (pin "G12") (pinfunction "OUT43_N_G12") (pintype "output"))
      (node (ref "X-NORTH") (pin "51") (pinfunction "51_51") (pintype "bidirectional"))
    )
    (net (code "33") (name "N14_N") (class "Default")
      (node (ref "SENSOR") (pin "F13") (pinfunction "OUT44_P_F13") (pintype "output"))
      (node (ref "X-NORTH") (pin "58") (pinfunction "58_58") (pintype "bidirectional"))
    )
    (net (code "34") (name "N14_P") (class "Default")
      (node (ref "SENSOR") (pin "F12") (pinfunction "OUT44_N_F12") (pintype "output"))
      (node (ref "X-NORTH") (pin "56") (pinfunction "56_56") (pintype "bidirectional"))
    )
    (net (code "35") (name "N15_N") (class "Default")
      (node (ref "SENSOR") (pin "H14") (pinfunction "OUT45_P_H14") (pintype "output"))
      (node (ref "X-NORTH") (pin "59") (pinfunction "59_59") (pintype "bidirectional"))
    )
    (net (code "36") (name "N15_P") (class "Default")
      (node (ref "SENSOR") (pin "H13") (pinfunction "OUT45_N_H13") (pintype "output"))
      (node (ref "X-NORTH") (pin "57") (pinfunction "57_57") (pintype "bidirectional"))
    )
    (net (code "37") (name "N16_N") (class "Default")
      (node (ref "SENSOR") (pin "E14") (pinfunction "OUT46_P_E14") (pintype "output"))
      (node (ref "X-NORTH") (pin "64") (pinfunction "64_64") (pintype "bidirectional"))
    )
    (net (code "38") (name "N16_P") (class "Default")
      (node (ref "SENSOR") (pin "E13") (pinfunction "OUT46_N_E13") (pintype "output"))
      (node (ref "X-NORTH") (pin "62") (pinfunction "62_62") (pintype "bidirectional"))
    )
    (net (code "39") (name "N17_N") (class "Default")
      (node (ref "SENSOR") (pin "G15") (pinfunction "OUT47_P_G15") (pintype "output"))
      (node (ref "X-NORTH") (pin "65") (pinfunction "65_65") (pintype "bidirectional"))
    )
    (net (code "40") (name "N17_P") (class "Default")
      (node (ref "SENSOR") (pin "G14") (pinfunction "OUT47_N_G14") (pintype "output"))
      (node (ref "X-NORTH") (pin "63") (pinfunction "63_63") (pintype "bidirectional"))
    )
    (net (code "41") (name "N18_N") (class "Default")
      (node (ref "SENSOR") (pin "F15") (pinfunction "OUT48_P_F15") (pintype "output"))
      (node (ref "X-NORTH") (pin "70") (pinfunction "70_70") (pintype "bidirectional"))
    )
    (net (code "42") (name "N18_P") (class "Default")
      (node (ref "SENSOR") (pin "F14") (pinfunction "OUT48_N_F14") (pintype "output"))
      (node (ref "X-NORTH") (pin "68") (pinfunction "68_68") (pintype "bidirectional"))
    )
    (net (code "43") (name "N19_N") (class "Default")
      (node (ref "SENSOR") (pin "G17") (pinfunction "OUT50_P_G17") (pintype "output"))
      (node (ref "X-NORTH") (pin "71") (pinfunction "71_71") (pintype "bidirectional"))
    )
    (net (code "44") (name "N19_P") (class "Default")
      (node (ref "SENSOR") (pin "G16") (pinfunction "OUT50_N_G16") (pintype "output"))
      (node (ref "X-NORTH") (pin "69") (pinfunction "69_69") (pintype "bidirectional"))
    )
    (net (code "45") (name "N20_N") (class "Default")
      (node (ref "SENSOR") (pin "F17") (pinfunction "OUT49_P_F17") (pintype "output"))
      (node (ref "X-NORTH") (pin "76") (pinfunction "76_76") (pintype "bidirectional"))
    )
    (net (code "46") (name "N20_P") (class "Default")
      (node (ref "SENSOR") (pin "F16") (pinfunction "OUT49_N_F16") (pintype "output"))
      (node (ref "X-NORTH") (pin "74") (pinfunction "74_74") (pintype "bidirectional"))
    )
    (net (code "47") (name "N21_N") (class "Default")
      (node (ref "SENSOR") (pin "H18") (pinfunction "OUT52_P_H18") (pintype "output"))
      (node (ref "X-NORTH") (pin "77") (pinfunction "77_77") (pintype "bidirectional"))
    )
    (net (code "48") (name "N21_P") (class "Default")
      (node (ref "SENSOR") (pin "H17") (pinfunction "OUT52_N_H17") (pintype "output"))
      (node (ref "X-NORTH") (pin "75") (pinfunction "75_75") (pintype "bidirectional"))
    )
    (net (code "49") (name "N22_N") (class "Default")
      (node (ref "SENSOR") (pin "E18") (pinfunction "OUT51_P_E18") (pintype "output"))
      (node (ref "X-NORTH") (pin "82") (pinfunction "82_82") (pintype "bidirectional"))
    )
    (net (code "50") (name "N22_P") (class "Default")
      (node (ref "SENSOR") (pin "E17") (pinfunction "OUT51_N_E17") (pintype "output"))
      (node (ref "X-NORTH") (pin "80") (pinfunction "80_80") (pintype "bidirectional"))
    )
    (net (code "51") (name "N23_N") (class "Default")
      (node (ref "SENSOR") (pin "G19") (pinfunction "OUT54_P_G19") (pintype "output"))
      (node (ref "X-NORTH") (pin "83") (pinfunction "83_83") (pintype "bidirectional"))
    )
    (net (code "52") (name "N23_P") (class "Default")
      (node (ref "SENSOR") (pin "G18") (pinfunction "OUT54_N_G18") (pintype "output"))
      (node (ref "X-NORTH") (pin "81") (pinfunction "81_81") (pintype "bidirectional"))
    )
    (net (code "53") (name "N24_N") (class "Default")
      (node (ref "SENSOR") (pin "F19") (pinfunction "OUT53_P_F19") (pintype "output"))
      (node (ref "X-NORTH") (pin "88") (pinfunction "88_88") (pintype "bidirectional"))
    )
    (net (code "54") (name "N24_P") (class "Default")
      (node (ref "SENSOR") (pin "F18") (pinfunction "OUT53_N_F18") (pintype "output"))
      (node (ref "X-NORTH") (pin "86") (pinfunction "86_86") (pintype "bidirectional"))
    )
    (net (code "55") (name "N25_N") (class "Default")
      (node (ref "SENSOR") (pin "H20") (pinfunction "OUT56_P_H20") (pintype "output"))
      (node (ref "X-NORTH") (pin "89") (pinfunction "89_89") (pintype "bidirectional"))
    )
    (net (code "56") (name "N25_P") (class "Default")
      (node (ref "SENSOR") (pin "H19") (pinfunction "OUT56_N_H19") (pintype "output"))
      (node (ref "X-NORTH") (pin "87") (pinfunction "87_87") (pintype "bidirectional"))
    )
    (net (code "57") (name "N26_N") (class "Default")
      (node (ref "SENSOR") (pin "E20") (pinfunction "OUT55_P_E20") (pintype "output"))
      (node (ref "X-NORTH") (pin "94") (pinfunction "94_94") (pintype "bidirectional"))
    )
    (net (code "58") (name "N26_P") (class "Default")
      (node (ref "SENSOR") (pin "E19") (pinfunction "OUT55_N_E19") (pintype "output"))
      (node (ref "X-NORTH") (pin "92") (pinfunction "92_92") (pintype "bidirectional"))
    )
    (net (code "59") (name "N27_N") (class "Default")
      (node (ref "SENSOR") (pin "G21") (pinfunction "OUT58_P_G21") (pintype "output"))
      (node (ref "X-NORTH") (pin "95") (pinfunction "95_95") (pintype "bidirectional"))
    )
    (net (code "60") (name "N27_P") (class "Default")
      (node (ref "SENSOR") (pin "G20") (pinfunction "OUT58_N_G20") (pintype "output"))
      (node (ref "X-NORTH") (pin "93") (pinfunction "93_93") (pintype "bidirectional"))
    )
    (net (code "61") (name "N28_N") (class "Default")
      (node (ref "SENSOR") (pin "F21") (pinfunction "OUT57_P_F21") (pintype "output"))
      (node (ref "X-NORTH") (pin "100") (pinfunction "100_100") (pintype "bidirectional"))
    )
    (net (code "62") (name "N28_P") (class "Default")
      (node (ref "SENSOR") (pin "F20") (pinfunction "OUT57_N_F20") (pintype "output"))
      (node (ref "X-NORTH") (pin "98") (pinfunction "98_98") (pintype "bidirectional"))
    )
    (net (code "63") (name "N29_N") (class "Default")
      (node (ref "SENSOR") (pin "G23") (pinfunction "OUT61_P_G23") (pintype "output"))
      (node (ref "X-NORTH") (pin "101") (pinfunction "101_101") (pintype "bidirectional"))
    )
    (net (code "64") (name "N29_P") (class "Default")
      (node (ref "SENSOR") (pin "G22") (pinfunction "OUT61_N_G22") (pintype "output"))
      (node (ref "X-NORTH") (pin "99") (pinfunction "99_99") (pintype "bidirectional"))
    )
    (net (code "65") (name "N30_N") (class "Default")
      (node (ref "SENSOR") (pin "E22") (pinfunction "OUT59_P_E22") (pintype "output"))
      (node (ref "X-NORTH") (pin "106") (pinfunction "106_106") (pintype "bidirectional"))
    )
    (net (code "66") (name "N30_P") (class "Default")
      (node (ref "SENSOR") (pin "E21") (pinfunction "OUT59_N_E21") (pintype "output"))
      (node (ref "X-NORTH") (pin "104") (pinfunction "104_104") (pintype "bidirectional"))
    )
    (net (code "67") (name "N31_N") (class "Default")
      (node (ref "SENSOR") (pin "H24") (pinfunction "OUT63_P_H24") (pintype "output"))
      (node (ref "X-NORTH") (pin "107") (pinfunction "107_107") (pintype "bidirectional"))
    )
    (net (code "68") (name "N31_P") (class "Default")
      (node (ref "SENSOR") (pin "H23") (pinfunction "OUT63_N_H23") (pintype "output"))
      (node (ref "X-NORTH") (pin "105") (pinfunction "105_105") (pintype "bidirectional"))
    )
    (net (code "69") (name "N32_N") (class "Default")
      (node (ref "SENSOR") (pin "F23") (pinfunction "OUT60_P_F23") (pintype "output"))
      (node (ref "X-NORTH") (pin "112") (pinfunction "112_112") (pintype "bidirectional"))
    )
    (net (code "70") (name "N32_P") (class "Default")
      (node (ref "SENSOR") (pin "F22") (pinfunction "OUT60_N_F22") (pintype "output"))
      (node (ref "X-NORTH") (pin "110") (pinfunction "110_110") (pintype "bidirectional"))
    )
    (net (code "71") (name "N33_N") (class "Default")
      (node (ref "SENSOR") (pin "G25") (pinfunction "OUT64_P_G25") (pintype "output"))
      (node (ref "X-NORTH") (pin "113") (pinfunction "113_113") (pintype "bidirectional"))
    )
    (net (code "72") (name "N33_P") (class "Default")
      (node (ref "SENSOR") (pin "G24") (pinfunction "OUT64_N_G24") (pintype "output"))
      (node (ref "X-NORTH") (pin "111") (pinfunction "111_111") (pintype "bidirectional"))
    )
    (net (code "73") (name "N34_N") (class "Default")
      (node (ref "SENSOR") (pin "E24") (pinfunction "OUT62_P_E24") (pintype "output"))
      (node (ref "X-NORTH") (pin "118") (pinfunction "118_118") (pintype "bidirectional"))
    )
    (net (code "74") (name "N34_P") (class "Default")
      (node (ref "SENSOR") (pin "E23") (pinfunction "OUT62_N_E23") (pintype "output"))
      (node (ref "X-NORTH") (pin "116") (pinfunction "116_116") (pintype "bidirectional"))
    )
    (net (code "75") (name "N35_N") (class "Default")
      (node (ref "U6") (pin "4") (pinfunction "A4_4") (pintype "bidirectional"))
      (node (ref "X-NORTH") (pin "119") (pinfunction "119_119") (pintype "bidirectional"))
    )
    (net (code "76") (name "N35_P") (class "Default")
      (node (ref "U6") (pin "3") (pinfunction "A3_3") (pintype "bidirectional"))
      (node (ref "X-NORTH") (pin "117") (pinfunction "117_117") (pintype "bidirectional"))
    )
    (net (code "77") (name "N36_N") (class "Default")
      (node (ref "X-NORTH") (pin "124") (pinfunction "124_124") (pintype "bidirectional"))
    )
    (net (code "78") (name "N36_P") (class "Default")
      (node (ref "X-NORTH") (pin "122") (pinfunction "122_122") (pintype "bidirectional"))
    )
    (net (code "79") (name "N37_N") (class "Default")
      (node (ref "U5") (pin "3") (pinfunction "A3_3") (pintype "bidirectional"))
      (node (ref "X-NORTH") (pin "125") (pinfunction "125_125") (pintype "bidirectional"))
    )
    (net (code "80") (name "N37_P") (class "Default")
      (node (ref "U5") (pin "4") (pinfunction "A4_4") (pintype "bidirectional"))
      (node (ref "X-NORTH") (pin "123") (pinfunction "123_123") (pintype "bidirectional"))
    )
    (net (code "81") (name "N38_N") (class "Default")
      (node (ref "U6") (pin "2") (pinfunction "A2_2") (pintype "bidirectional"))
      (node (ref "X-NORTH") (pin "130") (pinfunction "130_130") (pintype "bidirectional"))
    )
    (net (code "82") (name "N38_P") (class "Default")
      (node (ref "U6") (pin "1") (pinfunction "A1_1") (pintype "bidirectional"))
      (node (ref "X-NORTH") (pin "128") (pinfunction "128_128") (pintype "bidirectional"))
    )
    (net (code "83") (name "N39_N") (class "Default")
      (node (ref "U5") (pin "1") (pinfunction "A1_1") (pintype "bidirectional"))
      (node (ref "X-NORTH") (pin "131") (pinfunction "131_131") (pintype "bidirectional"))
    )
    (net (code "84") (name "N39_P") (class "Default")
      (node (ref "U5") (pin "2") (pinfunction "A2_2") (pintype "bidirectional"))
      (node (ref "X-NORTH") (pin "129") (pinfunction "129_129") (pintype "bidirectional"))
    )
    (net (code "85") (name "N_CHK_EN") (class "Default")
      (node (ref "X-NORTH") (pin "8") (pinfunction "8_8") (pintype "bidirectional"))
    )
    (net (code "86") (name "N_CHK_V") (class "Default")
      (node (ref "C2") (pin "1") (pinfunction "1_1") (pintype "passive"))
      (node (ref "C3") (pin "1") (pinfunction "1_1") (pintype "passive"))
      (node (ref "C4") (pin "1") (pinfunction "1_1") (pintype "passive"))
      (node (ref "R19") (pin "1") (pinfunction "1_1") (pintype "passive"))
      (node (ref "TP1") (pin "TP") (pinfunction "TP_TP") (pintype "input"))
      (node (ref "UNE") (pin "8") (pinfunction "VDD_8") (pintype "power_in"))
      (node (ref "UNN") (pin "8") (pinfunction "VDD_8") (pintype "power_in"))
      (node (ref "UNW") (pin "8") (pinfunction "VDD_8") (pintype "power_in"))
      (node (ref "X-NORTH") (pin "10") (pinfunction "10_10") (pintype "bidirectional"))
    )
    (net (code "87") (name "N_I2C_EN") (class "Default")
      (node (ref "X-NORTH") (pin "137") (pinfunction "137_137") (pintype "bidirectional"))
    )
    (net (code "88") (name "N_I2C_V") (class "Default")
      (node (ref "C1") (pin "1") (pinfunction "1_1") (pintype "passive"))
      (node (ref "R1X") (pin "1") (pinfunction "1_1") (pintype "passive"))
      (node (ref "UEP") (pin "8") (pinfunction "VCC_8") (pintype "power_in"))
      (node (ref "X-NORTH") (pin "135") (pinfunction "135_135") (pintype "bidirectional"))
    )
    (net (code "89") (name "N_REF") (class "Default")
      (node (ref "R19") (pin "2") (pinfunction "2_2") (pintype "passive"))
      (node (ref "TP2") (pin "TP") (pinfunction "TP_TP") (pintype "input"))
      (node (ref "U1") (pin "1") (pinfunction "CATHODE_1") (pintype "output"))
      (node (ref "U1") (pin "3") (pinfunction "REF_3") (pintype "input"))
      (node (ref "UNE") (pin "2") (pinfunction "VINA-_2") (pintype "input"))
      (node (ref "UNE") (pin "5") (pinfunction "VINB+_5") (pintype "input"))
      (node (ref "UNN") (pin "2") (pinfunction "VINA-_2") (pintype "input"))
      (node (ref "UNN") (pin "5") (pinfunction "VINB+_5") (pintype "input"))
      (node (ref "UNW") (pin "2") (pinfunction "VINA-_2") (pintype "input"))
      (node (ref "UNW") (pin "5") (pinfunction "VINB+_5") (pintype "input"))
    )
    (net (code "90") (name "N_SCK") (class "Default")
      (node (ref "U4") (pin "4") (pinfunction "A4_4") (pintype "bidirectional"))
      (node (ref "X-NORTH") (pin "144") (pinfunction "144_144") (pintype "bidirectional"))
    )
    (net (code "91") (name "N_SCL") (class "Default")
      (node (ref "UEP") (pin "6") (pinfunction "SCL_6") (pintype "input"))
      (node (ref "X-NORTH") (pin "143") (pinfunction "143_143") (pintype "bidirectional"))
    )
    (net (code "92") (name "N_SDA") (class "Default")
      (node (ref "UEP") (pin "5") (pinfunction "SDA_5") (pintype "bidirectional"))
      (node (ref "X-NORTH") (pin "141") (pinfunction "141_141") (pintype "bidirectional"))
    )
    (net (code "93") (name "N_SDI") (class "Default")
      (node (ref "U4") (pin "2") (pinfunction "A2_2") (pintype "bidirectional"))
      (node (ref "X-NORTH") (pin "140") (pinfunction "140_140") (pintype "bidirectional"))
    )
    (net (code "94") (name "N_SDO") (class "Default")
      (node (ref "U4") (pin "3") (pinfunction "A3_3") (pintype "bidirectional"))
      (node (ref "X-NORTH") (pin "142") (pinfunction "142_142") (pintype "bidirectional"))
    )
    (net (code "95") (name "N_SPI_EN") (class "Default")
      (node (ref "U4") (pin "1") (pinfunction "A1_1") (pintype "bidirectional"))
      (node (ref "X-NORTH") (pin "136") (pinfunction "136_136") (pintype "bidirectional"))
    )
    (net (code "96") (name "N_SPI_V") (class "Default")
      (node (ref "C59") (pin "1") (pinfunction "1_1") (pintype "passive"))
      (node (ref "U4") (pin "14") (pinfunction "VCCA_14") (pintype "power_in"))
      (node (ref "U4") (pin "15") (pinfunction "DIR1_15") (pintype "input"))
      (node (ref "U4") (pin "5") (pinfunction "DIR3_5") (pintype "input"))
      (node (ref "U4") (pin "6") (pinfunction "DIR4_6") (pintype "input"))
      (node (ref "X-NORTH") (pin "134") (pinfunction "134_134") (pintype "bidirectional"))
    )
    (net (code "97") (name "N_VE") (class "Default")
      (node (ref "C22") (pin "1") (pinfunction "1_1") (pintype "passive"))
      (node (ref "C23") (pin "1") (pinfunction "1_1") (pintype "passive"))
      (node (ref "C24") (pin "1") (pinfunction "1_1") (pintype "passive"))
      (node (ref "C25") (pin "1") (pinfunction "1_1") (pintype "passive"))
      (node (ref "C26") (pin "1") (pinfunction "1_1") (pintype "passive"))
      (node (ref "C27") (pin "1") (pinfunction "1_1") (pintype "passive"))
      (node (ref "C28") (pin "1") (pinfunction "1_1") (pintype "passive"))
      (node (ref "C50") (pin "1") (pinfunction "1_1") (pintype "passive"))
      (node (ref "C51") (pin "1") (pinfunction "1_1") (pintype "passive"))
      (node (ref "C52") (pin "1") (pinfunction "1_1") (pintype "passive"))
      (node (ref "C53") (pin "1") (pinfunction "1_1") (pintype "passive"))
      (node (ref "C54") (pin "1") (pinfunction "1_1") (pintype "passive"))
      (node (ref "C55") (pin "1") (pinfunction "1_1") (pintype "passive"))
      (node (ref "C56") (pin "1") (pinfunction "1_1") (pintype "passive"))
      (node (ref "C67") (pin "1") (pinfunction "1_1") (pintype "passive"))
      (node (ref "C69") (pin "1") (pinfunction "1_1") (pintype "passive"))
      (node (ref "C75") (pin "1") (pinfunction "1_1") (pintype "passive"))
      (node (ref "C76") (pin "1") (pinfunction "1_1") (pintype "passive"))
      (node (ref "C77") (pin "1") (pinfunction "1_1") (pintype "passive"))
      (node (ref "C84") (pin "1") (pinfunction "1_1") (pintype "passive"))
      (node (ref "C85") (pin "1") (pinfunction "1_1") (pintype "passive"))
      (node (ref "C86") (pin "1") (pinfunction "1_1") (pintype "passive"))
      (node (ref "C93") (pin "1") (pinfunction "1_1") (pintype "passive"))
      (node (ref "SENSOR") (pin "C26") (pinfunction "VDD33_C26") (pintype "power_in"))
      (node (ref "SENSOR") (pin "C27") (pinfunction "VDD33_C27") (pintype "power_in"))
      (node (ref "SENSOR") (pin "D26") (pinfunction "VDD33_D26") (pintype "power_in"))
      (node (ref "SENSOR") (pin "D3") (pinfunction "VDD33_D3") (pintype "power_in"))
      (node (ref "SENSOR") (pin "E26") (pinfunction "VDD33_E26") (pintype "power_in"))
      (node (ref "SENSOR") (pin "F26") (pinfunction "VDD33_F26") (pintype "power_in"))
      (node (ref "SENSOR") (pin "F5") (pinfunction "VDD33_F5") (pintype "power_in"))
      (node (ref "TP7") (pin "TP") (pinfunction "TP_TP") (pintype "input"))
      (node (ref "U4") (pin "13") (pinfunction "VCCB_13") (pintype "power_in"))
      (node (ref "U5") (pin "13") (pinfunction "VCCB_13") (pintype "power_in"))
      (node (ref "U6") (pin "13") (pinfunction "VCCB_13") (pintype "power_in"))
      (node (ref "X-NORTH") (pin "109") (pinfunction "109_109") (pintype "bidirectional"))
      (node (ref "X-NORTH") (pin "115") (pinfunction "115_115") (pintype "bidirectional"))
      (node (ref "X-NORTH") (pin "121") (pinfunction "121_121") (pintype "bidirectional"))
      (node (ref "X-NORTH") (pin "127") (pinfunction "127_127") (pintype "bidirectional"))
      (node (ref "X-NORTH") (pin "133") (pinfunction "133_133") (pintype "bidirectional"))
    )
    (net (code "98") (name "N_VE_CV") (class "Default")
      (node (ref "C10") (pin "1") (pinfunction "1_1") (pintype "passive"))
      (node (ref "R7") (pin "1") (pinfunction "1_1") (pintype "passive"))
      (node (ref "X-NORTH") (pin "6") (pinfunction "6_6") (pintype "bidirectional"))
    )
    (net (code "99") (name "N_VE_OV") (class "Default")
      (node (ref "UNE") (pin "7") (pinfunction "OUTB_7") (pintype "output"))
      (node (ref "X-NORTH") (pin "5") (pinfunction "5_5") (pintype "bidirectional"))
    )
    (net (code "100") (name "N_VE_UV") (class "Default")
      (node (ref "UNE") (pin "1") (pinfunction "OUTA_1") (pintype "output"))
      (node (ref "X-NORTH") (pin "11") (pinfunction "11_11") (pintype "bidirectional"))
    )
    (net (code "101") (name "N_VN") (class "Default")
      (node (ref "C31") (pin "1") (pinfunction "1_1") (pintype "passive"))
      (node (ref "C32") (pin "1") (pinfunction "1_1") (pintype "passive"))
      (node (ref "C33") (pin "1") (pinfunction "1_1") (pintype "passive"))
      (node (ref "C34") (pin "1") (pinfunction "1_1") (pintype "passive"))
      (node (ref "C35") (pin "1") (pinfunction "1_1") (pintype "passive"))
      (node (ref "C36") (pin "1") (pinfunction "1_1") (pintype "passive"))
      (node (ref "C37") (pin "1") (pinfunction "1_1") (pintype "passive"))
      (node (ref "C38") (pin "1") (pinfunction "1_1") (pintype "passive"))
      (node (ref "C39") (pin "1") (pinfunction "1_1") (pintype "passive"))
      (node (ref "C40") (pin "1") (pinfunction "1_1") (pintype "passive"))
      (node (ref "C41") (pin "1") (pinfunction "1_1") (pintype "passive"))
      (node (ref "C42") (pin "1") (pinfunction "1_1") (pintype "passive"))
      (node (ref "C43") (pin "1") (pinfunction "1_1") (pintype "passive"))
      (node (ref "C44") (pin "1") (pinfunction "1_1") (pintype "passive"))
      (node (ref "C68") (pin "1") (pinfunction "1_1") (pintype "passive"))
      (node (ref "C70") (pin "1") (pinfunction "1_1") (pintype "passive"))
      (node (ref "C78") (pin "1") (pinfunction "1_1") (pintype "passive"))
      (node (ref "C79") (pin "1") (pinfunction "1_1") (pintype "passive"))
      (node (ref "C80") (pin "1") (pinfunction "1_1") (pintype "passive"))
      (node (ref "C87") (pin "1") (pinfunction "1_1") (pintype "passive"))
      (node (ref "C88") (pin "1") (pinfunction "1_1") (pintype "passive"))
      (node (ref "C89") (pin "1") (pinfunction "1_1") (pintype "passive"))
      (node (ref "SENSOR") (pin "A10") (pinfunction "VDD18_A10") (pintype "power_in"))
      (node (ref "SENSOR") (pin "A15") (pinfunction "VDD18_A15") (pintype "power_in"))
      (node (ref "SENSOR") (pin "A16") (pinfunction "VDD18_A16") (pintype "power_in"))
      (node (ref "SENSOR") (pin "A22") (pinfunction "VDD18_A22") (pintype "power_in"))
      (node (ref "SENSOR") (pin "A26") (pinfunction "VDD18_A26") (pintype "power_in"))
      (node (ref "SENSOR") (pin "A27") (pinfunction "VDD18_A27") (pintype "power_in"))
      (node (ref "SENSOR") (pin "B4") (pinfunction "VDD18_B4") (pintype "power_in"))
      (node (ref "SENSOR") (pin "E1") (pinfunction "VDD18_PLL_E1") (pintype "power_in"))
      (node (ref "SENSOR") (pin "H10") (pinfunction "VDD18_H10") (pintype "power_in"))
      (node (ref "SENSOR") (pin "H15") (pinfunction "VDD18_H15") (pintype "power_in"))
      (node (ref "SENSOR") (pin "H16") (pinfunction "VDD18_H16") (pintype "power_in"))
      (node (ref "SENSOR") (pin "H22") (pinfunction "VDD18_H22") (pintype "power_in"))
      (node (ref "SENSOR") (pin "H26") (pinfunction "VDD18_H26") (pintype "power_in"))
      (node (ref "SENSOR") (pin "H5") (pinfunction "VDD18_H5") (pintype "power_in"))
      (node (ref "TP5") (pin "TP") (pinfunction "TP_TP") (pintype "input"))
      (node (ref "U5") (pin "14") (pinfunction "VCCA_14") (pintype "power_in"))
      (node (ref "U5") (pin "15") (pinfunction "DIR1_15") (pintype "input"))
      (node (ref "U5") (pin "16") (pinfunction "DIR2_16") (pintype "input"))
      (node (ref "U5") (pin "5") (pinfunction "DIR3_5") (pintype "input"))
      (node (ref "U6") (pin "14") (pinfunction "VCCA_14") (pintype "power_in"))
      (node (ref "U6") (pin "15") (pinfunction "DIR1_15") (pintype "input"))
      (node (ref "U6") (pin "5") (pinfunction "DIR3_5") (pintype "input"))
      (node (ref "U6") (pin "6") (pinfunction "DIR4_6") (pintype "input"))
      (node (ref "X-NORTH") (pin "49") (pinfunction "49_49") (pintype "bidirectional"))
      (node (ref "X-NORTH") (pin "55") (pinfunction "55_55") (pintype "bidirectional"))
      (node (ref "X-NORTH") (pin "61") (pinfunction "61_61") (pintype "bidirectional"))
      (node (ref "X-NORTH") (pin "67") (pinfunction "67_67") (pintype "bidirectional"))
      (node (ref "X-NORTH") (pin "73") (pinfunction "73_73") (pintype "bidirectional"))
      (node (ref "X-NORTH") (pin "79") (pinfunction "79_79") (pintype "bidirectional"))
      (node (ref "X-NORTH") (pin "85") (pinfunction "85_85") (pintype "bidirectional"))
      (node (ref "X-NORTH") (pin "91") (pinfunction "91_91") (pintype "bidirectional"))
      (node (ref "X-NORTH") (pin "97") (pinfunction "97_97") (pintype "bidirectional"))
    )
    (net (code "102") (name "N_VN_CV") (class "Default")
      (node (ref "C9") (pin "1") (pinfunction "1_1") (pintype "passive"))
      (node (ref "R4") (pin "1") (pinfunction "1_1") (pintype "passive"))
      (node (ref "X-NORTH") (pin "4") (pinfunction "4_4") (pintype "bidirectional"))
    )
    (net (code "103") (name "N_VN_OV") (class "Default")
      (node (ref "UNN") (pin "7") (pinfunction "OUTB_7") (pintype "output"))
      (node (ref "X-NORTH") (pin "3") (pinfunction "3_3") (pintype "bidirectional"))
    )
    (net (code "104") (name "N_VN_UV") (class "Default")
      (node (ref "UNN") (pin "1") (pinfunction "OUTA_1") (pintype "output"))
      (node (ref "X-NORTH") (pin "9") (pinfunction "9_9") (pintype "bidirectional"))
    )
    (net (code "105") (name "N_VW") (class "Default")
      (node (ref "C57") (pin "1") (pinfunction "1_1") (pintype "passive"))
      (node (ref "C58") (pin "1") (pinfunction "1_1") (pintype "passive"))
      (node (ref "C92") (pin "1") (pinfunction "1_1") (pintype "passive"))
      (node (ref "SENSOR") (pin "E2") (pinfunction "VDD_RES_E2") (pintype "power_in"))
      (node (ref "SENSOR") (pin "G4") (pinfunction "VDD_RES_G4") (pintype "power_in"))
      (node (ref "TP8") (pin "TP") (pinfunction "TP_TP") (pintype "input"))
      (node (ref "X-NORTH") (pin "13") (pinfunction "13_13") (pintype "bidirectional"))
      (node (ref "X-NORTH") (pin "19") (pinfunction "19_19") (pintype "bidirectional"))
      (node (ref "X-NORTH") (pin "25") (pinfunction "25_25") (pintype "bidirectional"))
      (node (ref "X-NORTH") (pin "31") (pinfunction "31_31") (pintype "bidirectional"))
      (node (ref "X-NORTH") (pin "37") (pinfunction "37_37") (pintype "bidirectional"))
    )
    (net (code "106") (name "N_VW_CV") (class "Default")
      (node (ref "C8") (pin "1") (pinfunction "1_1") (pintype "passive"))
      (node (ref "R1") (pin "1") (pinfunction "1_1") (pintype "passive"))
      (node (ref "X-NORTH") (pin "2") (pinfunction "2_2") (pintype "bidirectional"))
    )
    (net (code "107") (name "N_VW_OV") (class "Default")
      (node (ref "UNW") (pin "7") (pinfunction "OUTB_7") (pintype "output"))
      (node (ref "X-NORTH") (pin "1") (pinfunction "1_1") (pintype "bidirectional"))
    )
    (net (code "108") (name "N_VW_UV") (class "Default")
      (node (ref "UNW") (pin "1") (pinfunction "OUTA_1") (pintype "output"))
      (node (ref "X-NORTH") (pin "7") (pinfunction "7_7") (pintype "bidirectional"))
    )
    (net (code "109") (name "Net-(SENSORB-CMDN)") (class "Default")
      (node (ref "C61") (pin "1") (pinfunction "1_1") (pintype "passive"))
      (node (ref "SENSOR") (pin "F1") (pinfunction "CMDN_F1") (pintype "bidirectional"))
    )
    (net (code "110") (name "Net-(SENSORB-CMDP)") (class "Default")
      (node (ref "C22") (pin "2") (pinfunction "2_2") (pintype "passive"))
      (node (ref "SENSOR") (pin "F2") (pinfunction "CMDP_F2") (pintype "bidirectional"))
    )
    (net (code "111") (name "Net-(SENSORB-CMDP_COMP)") (class "Default")
      (node (ref "C28") (pin "2") (pinfunction "2_2") (pintype "passive"))
      (node (ref "SENSOR") (pin "H3") (pinfunction "CMDP_COMP_H3") (pintype "bidirectional"))
    )
    (net (code "112") (name "Net-(SENSORB-CMDP_COMP_INV)") (class "Default")
      (node (ref "C27") (pin "2") (pinfunction "2_2") (pintype "passive"))
      (node (ref "SENSOR") (pin "F3") (pinfunction "CMDP_COMP_INV_F3") (pintype "bidirectional"))
    )
    (net (code "113") (name "Net-(SENSORB-CMD_COLAMP)") (class "Default")
      (node (ref "C25") (pin "2") (pinfunction "2_2") (pintype "passive"))
      (node (ref "SENSOR") (pin "C6") (pinfunction "CMD_COLAMP_C6") (pintype "bidirectional"))
    )
    (net (code "114") (name "Net-(SENSORB-CMD_COL_LOAD)") (class "Default")
      (node (ref "C23") (pin "2") (pinfunction "2_2") (pintype "passive"))
      (node (ref "SENSOR") (pin "B1") (pinfunction "CMD_COL_LOAD_B1") (pintype "bidirectional"))
    )
    (net (code "115") (name "Net-(SENSORB-CMD_COL_PC)") (class "Default")
      (node (ref "C26") (pin "2") (pinfunction "2_2") (pintype "passive"))
      (node (ref "SENSOR") (pin "D1") (pinfunction "CMD_COL_PC_D1") (pintype "bidirectional"))
    )
    (net (code "116") (name "Net-(SENSORB-CMD_LVDS)") (class "Default")
      (node (ref "C62") (pin "1") (pinfunction "1_1") (pintype "passive"))
      (node (ref "SENSOR") (pin "C1") (pinfunction "CMD_LVDS_C1") (pintype "bidirectional"))
    )
    (net (code "117") (name "Net-(SENSORB-CMD_RAMP)") (class "Default")
      (node (ref "C24") (pin "2") (pinfunction "2_2") (pintype "passive"))
      (node (ref "SENSOR") (pin "B29") (pinfunction "CMD_RAMP_B29") (pintype "bidirectional"))
    )
    (net (code "118") (name "Net-(SENSORB-VBGAP)") (class "Default")
      (node (ref "C64") (pin "1") (pinfunction "1_1") (pintype "passive"))
      (node (ref "SENSOR") (pin "C29") (pinfunction "VBGAP_C29") (pintype "bidirectional"))
    )
    (net (code "119") (name "Net-(SENSORB-VCLAMP)") (class "Default")
      (node (ref "C63") (pin "1") (pinfunction "1_1") (pintype "passive"))
      (node (ref "SENSOR") (pin "D4") (pinfunction "VCLAMP_D4") (pintype "bidirectional"))
    )
    (net (code "120") (name "Net-(SENSORB-VCLAMP_ADC)") (class "Default")
      (node (ref "C60") (pin "1") (pinfunction "1_1") (pintype "passive"))
      (node (ref "SENSOR") (pin "G2") (pinfunction "VCLAMP_ADC_G2") (pintype "bidirectional"))
    )
    (net (code "121") (name "Net-(SENSORB-VPCH_H)") (class "Default")
      (node (ref "C71") (pin "1") (pinfunction "1_1") (pintype "passive"))
      (node (ref "SENSOR") (pin "C4") (pinfunction "VPCH_H_C4") (pintype "bidirectional"))
    )
    (net (code "122") (name "Net-(SENSORB-VPCH_L)") (class "Default")
      (node (ref "C14") (pin "1") (pinfunction "1_1") (pintype "passive"))
      (node (ref "SENSOR") (pin "A4") (pinfunction "VPCH_L_A4") (pintype "bidirectional"))
    )
    (net (code "123") (name "Net-(SENSORB-VREF)") (class "Default")
      (node (ref "C29") (pin "1") (pinfunction "1_1") (pintype "passive"))
      (node (ref "SENSOR") (pin "A3") (pinfunction "VREF_A3") (pintype "bidirectional"))
    )
    (net (code "124") (name "Net-(SENSORB-VREF_ADC)") (class "Default")
      (node (ref "C30") (pin "1") (pinfunction "1_1") (pintype "passive"))
      (node (ref "SENSOR") (pin "B3") (pinfunction "VREF_ADC_B3") (pintype "bidirectional"))
    )
    (net (code "125") (name "Net-(SENSORB-VRES_L)") (class "Default")
      (node (ref "C15") (pin "1") (pinfunction "1_1") (pintype "passive"))
      (node (ref "SENSOR") (pin "D5") (pinfunction "VRES_L_D5") (pintype "bidirectional"))
    )
    (net (code "126") (name "Net-(SENSORB-VTF_LOW0)") (class "Default")
      (node (ref "C18") (pin "1") (pinfunction "1_1") (pintype "passive"))
      (node (ref "SENSOR") (pin "C5") (pinfunction "VTF_LOW0_C5") (pintype "bidirectional"))
    )
    (net (code "127") (name "Net-(SENSORB-VTF_LOW1)") (class "Default")
      (node (ref "C19") (pin "1") (pinfunction "1_1") (pintype "passive"))
      (node (ref "SENSOR") (pin "D6") (pinfunction "VTF_LOW1_D6") (pintype "bidirectional"))
    )
    (net (code "128") (name "Net-(SENSORB-VTF_LOW2)") (class "Default")
      (node (ref "C20") (pin "1") (pinfunction "1_1") (pintype "passive"))
      (node (ref "SENSOR") (pin "B30") (pinfunction "VTF_LOW2_B30") (pintype "bidirectional"))
    )
    (net (code "129") (name "Net-(SENSORB-VTF_LOW3)") (class "Default")
      (node (ref "C21") (pin "1") (pinfunction "1_1") (pintype "passive"))
      (node (ref "SENSOR") (pin "C30") (pinfunction "VTF_LOW3_C30") (pintype "bidirectional"))
    )
    (net (code "130") (name "Net-(U3-ADJ)") (class "Default")
      (node (ref "R21") (pin "1") (pinfunction "1_1") (pintype "passive"))
      (node (ref "R22") (pin "2") (pinfunction "2_2") (pintype "passive"))
      (node (ref "U3") (pin "5") (pinfunction "ADJ_5") (pintype "input"))
    )
    (net (code "131") (name "Net-(U6-B4)") (class "Default")
      (node (ref "TP9") (pin "TP") (pinfunction "TP_TP") (pintype "input"))
      (node (ref "U6") (pin "9") (pinfunction "B4_9") (pintype "bidirectional"))
    )
    (net (code "132") (name "Net-(UEP-WP)") (class "Default")
      (node (ref "R1X") (pin "2") (pinfunction "2_2") (pintype "passive"))
      (node (ref "R2X") (pin "1") (pinfunction "1_1") (pintype "passive"))
      (node (ref "UEP") (pin "7") (pinfunction "WP_7") (pintype "input"))
    )
    (net (code "133") (name "Net-(UNE-VINA+)") (class "Default")
      (node (ref "R7") (pin "2") (pinfunction "2_2") (pintype "passive"))
      (node (ref "R8") (pin "1") (pinfunction "1_1") (pintype "passive"))
      (node (ref "UNE") (pin "3") (pinfunction "VINA+_3") (pintype "input"))
    )
    (net (code "134") (name "Net-(UNE-VINB-)") (class "Default")
      (node (ref "R8") (pin "2") (pinfunction "2_2") (pintype "passive"))
      (node (ref "R9") (pin "1") (pinfunction "1_1") (pintype "passive"))
      (node (ref "UNE") (pin "6") (pinfunction "VINB-_6") (pintype "input"))
    )
    (net (code "135") (name "Net-(UNN-VINA+)") (class "Default")
      (node (ref "R4") (pin "2") (pinfunction "2_2") (pintype "passive"))
      (node (ref "R5") (pin "1") (pinfunction "1_1") (pintype "passive"))
      (node (ref "UNN") (pin "3") (pinfunction "VINA+_3") (pintype "input"))
    )
    (net (code "136") (name "Net-(UNN-VINB-)") (class "Default")
      (node (ref "R5") (pin "2") (pinfunction "2_2") (pintype "passive"))
      (node (ref "R6") (pin "1") (pinfunction "1_1") (pintype "passive"))
      (node (ref "UNN") (pin "6") (pinfunction "VINB-_6") (pintype "input"))
    )
    (net (code "137") (name "Net-(UNW-VINA+)") (class "Default")
      (node (ref "R1") (pin "2") (pinfunction "2_2") (pintype "passive"))
      (node (ref "R2") (pin "1") (pinfunction "1_1") (pintype "passive"))
      (node (ref "UNW") (pin "3") (pinfunction "VINA+_3") (pintype "input"))
    )
    (net (code "138") (name "Net-(UNW-VINB-)") (class "Default")
      (node (ref "R2") (pin "2") (pinfunction "2_2") (pintype "passive"))
      (node (ref "R3") (pin "1") (pinfunction "1_1") (pintype "passive"))
      (node (ref "UNW") (pin "6") (pinfunction "VINB-_6") (pintype "input"))
    )
    (net (code "139") (name "Net-(USE-VINA+)") (class "Default")
      (node (ref "R10") (pin "2") (pinfunction "2_2") (pintype "passive"))
      (node (ref "R11") (pin "1") (pinfunction "1_1") (pintype "passive"))
      (node (ref "USE") (pin "3") (pinfunction "VINA+_3") (pintype "input"))
    )
    (net (code "140") (name "Net-(USE-VINB-)") (class "Default")
      (node (ref "R11") (pin "2") (pinfunction "2_2") (pintype "passive"))
      (node (ref "R12") (pin "1") (pinfunction "1_1") (pintype "passive"))
      (node (ref "USE") (pin "6") (pinfunction "VINB-_6") (pintype "input"))
    )
    (net (code "141") (name "Net-(USS-VINA+)") (class "Default")
      (node (ref "R13") (pin "2") (pinfunction "2_2") (pintype "passive"))
      (node (ref "R14") (pin "1") (pinfunction "1_1") (pintype "passive"))
      (node (ref "USS") (pin "3") (pinfunction "VINA+_3") (pintype "input"))
    )
    (net (code "142") (name "Net-(USS-VINB-)") (class "Default")
      (node (ref "R14") (pin "2") (pinfunction "2_2") (pintype "passive"))
      (node (ref "R15") (pin "1") (pinfunction "1_1") (pintype "passive"))
      (node (ref "USS") (pin "6") (pinfunction "VINB-_6") (pintype "input"))
    )
    (net (code "143") (name "Net-(USW-VINA+)") (class "Default")
      (node (ref "R16") (pin "2") (pinfunction "2_2") (pintype "passive"))
      (node (ref "R17") (pin "1") (pinfunction "1_1") (pintype "passive"))
      (node (ref "USW") (pin "3") (pinfunction "VINA+_3") (pintype "input"))
    )
    (net (code "144") (name "Net-(USW-VINB-)") (class "Default")
      (node (ref "R17") (pin "2") (pinfunction "2_2") (pintype "passive"))
      (node (ref "R18") (pin "1") (pinfunction "1_1") (pintype "passive"))
      (node (ref "USW") (pin "6") (pinfunction "VINB-_6") (pintype "input"))
    )
    (net (code "145") (name "S00_N") (class "Default")
      (node (ref "X-SOUTH") (pin "16") (pinfunction "16_16") (pintype "bidirectional"))
    )
    (net (code "146") (name "S00_P") (class "Default")
      (node (ref "X-SOUTH") (pin "14") (pinfunction "14_14") (pintype "bidirectional"))
    )
    (net (code "147") (name "S01_N") (class "Default")
      (node (ref "X-SOUTH") (pin "17") (pinfunction "17_17") (pintype "bidirectional"))
    )
    (net (code "148") (name "S01_P") (class "Default")
      (node (ref "X-SOUTH") (pin "15") (pinfunction "15_15") (pintype "bidirectional"))
    )
    (net (code "149") (name "S02_N") (class "Default")
      (node (ref "X-SOUTH") (pin "22") (pinfunction "22_22") (pintype "bidirectional"))
    )
    (net (code "150") (name "S02_P") (class "Default")
      (node (ref "X-SOUTH") (pin "20") (pinfunction "20_20") (pintype "bidirectional"))
    )
    (net (code "151") (name "S03_N") (class "Default")
      (node (ref "X-SOUTH") (pin "23") (pinfunction "23_23") (pintype "bidirectional"))
    )
    (net (code "152") (name "S03_P") (class "Default")
      (node (ref "X-SOUTH") (pin "21") (pinfunction "21_21") (pintype "bidirectional"))
    )
    (net (code "153") (name "S04_N") (class "Default")
      (node (ref "SENSOR") (pin "C24") (pinfunction "OUT32_N_C24") (pintype "output"))
      (node (ref "X-SOUTH") (pin "28") (pinfunction "28_28") (pintype "bidirectional"))
    )
    (net (code "154") (name "S04_P") (class "Default")
      (node (ref "SENSOR") (pin "C25") (pinfunction "OUT32_P_C25") (pintype "output"))
      (node (ref "X-SOUTH") (pin "26") (pinfunction "26_26") (pintype "bidirectional"))
    )
    (net (code "155") (name "S05_N") (class "Default")
      (node (ref "X-SOUTH") (pin "29") (pinfunction "29_29") (pintype "bidirectional"))
    )
    (net (code "156") (name "S05_P") (class "Default")
      (node (ref "X-SOUTH") (pin "27") (pinfunction "27_27") (pintype "bidirectional"))
    )
    (net (code "157") (name "S06_N") (class "Default")
      (node (ref "SENSOR") (pin "D23") (pinfunction "OUT30_N_D23") (pintype "output"))
      (node (ref "X-SOUTH") (pin "34") (pinfunction "34_34") (pintype "bidirectional"))
    )
    (net (code "158") (name "S06_P") (class "Default")
      (node (ref "SENSOR") (pin "D24") (pinfunction "OUT30_P_D24") (pintype "output"))
      (node (ref "X-SOUTH") (pin "32") (pinfunction "32_32") (pintype "bidirectional"))
    )
    (net (code "159") (name "S07_N") (class "Default")
      (node (ref "SENSOR") (pin "B24") (pinfunction "OUT31_N_B24") (pintype "output"))
      (node (ref "X-SOUTH") (pin "35") (pinfunction "35_35") (pintype "bidirectional"))
    )
    (net (code "160") (name "S07_P") (class "Default")
      (node (ref "SENSOR") (pin "B25") (pinfunction "OUT31_P_B25") (pintype "output"))
      (node (ref "X-SOUTH") (pin "33") (pinfunction "33_33") (pintype "bidirectional"))
    )
    (net (code "161") (name "S08_N") (class "Default")
      (node (ref "SENSOR") (pin "D21") (pinfunction "OUT27_N_D21") (pintype "output"))
      (node (ref "X-SOUTH") (pin "40") (pinfunction "40_40") (pintype "bidirectional"))
    )
    (net (code "162") (name "S08_P") (class "Default")
      (node (ref "SENSOR") (pin "D22") (pinfunction "OUT27_P_D22") (pintype "output"))
      (node (ref "X-SOUTH") (pin "38") (pinfunction "38_38") (pintype "bidirectional"))
    )
    (net (code "163") (name "S09_N") (class "Default")
      (node (ref "SENSOR") (pin "A23") (pinfunction "OUT29_N_A23") (pintype "output"))
      (node (ref "X-SOUTH") (pin "41") (pinfunction "41_41") (pintype "bidirectional"))
    )
    (net (code "164") (name "S09_P") (class "Default")
      (node (ref "SENSOR") (pin "A24") (pinfunction "OUT29_P_A24") (pintype "output"))
      (node (ref "X-SOUTH") (pin "39") (pinfunction "39_39") (pintype "bidirectional"))
    )
    (net (code "165") (name "S10_N") (class "Default")
      (node (ref "SENSOR") (pin "C21") (pinfunction "OUT28_N_C21") (pintype "output"))
      (node (ref "X-SOUTH") (pin "46") (pinfunction "46_46") (pintype "bidirectional"))
    )
    (net (code "166") (name "S10_P") (class "Default")
      (node (ref "SENSOR") (pin "C22") (pinfunction "OUT28_P_C22") (pintype "output"))
      (node (ref "X-SOUTH") (pin "44") (pinfunction "44_44") (pintype "bidirectional"))
    )
    (net (code "167") (name "S11_N") (class "Default")
      (node (ref "SENSOR") (pin "B20") (pinfunction "OUT26_N_B20") (pintype "output"))
      (node (ref "X-SOUTH") (pin "47") (pinfunction "47_47") (pintype "bidirectional"))
    )
    (net (code "168") (name "S11_P") (class "Default")
      (node (ref "SENSOR") (pin "B21") (pinfunction "OUT26_P_B21") (pintype "output"))
      (node (ref "X-SOUTH") (pin "45") (pinfunction "45_45") (pintype "bidirectional"))
    )
    (net (code "169") (name "S12_N") (class "Default")
      (node (ref "SENSOR") (pin "D19") (pinfunction "OUT24_N_D19") (pintype "output"))
      (node (ref "X-SOUTH") (pin "52") (pinfunction "52_52") (pintype "bidirectional"))
    )
    (net (code "170") (name "S12_P") (class "Default")
      (node (ref "SENSOR") (pin "D20") (pinfunction "OUT24_P_D20") (pintype "output"))
      (node (ref "X-SOUTH") (pin "50") (pinfunction "50_50") (pintype "bidirectional"))
    )
    (net (code "171") (name "S13_N") (class "Default")
      (node (ref "SENSOR") (pin "A19") (pinfunction "OUT23_N_A19") (pintype "output"))
      (node (ref "X-SOUTH") (pin "53") (pinfunction "53_53") (pintype "bidirectional"))
    )
    (net (code "172") (name "S13_P") (class "Default")
      (node (ref "SENSOR") (pin "A20") (pinfunction "OUT23_P_A20") (pintype "output"))
      (node (ref "X-SOUTH") (pin "51") (pinfunction "51_51") (pintype "bidirectional"))
    )
    (net (code "173") (name "S14_N") (class "Default")
      (node (ref "SENSOR") (pin "C19") (pinfunction "OUT25_N_C19") (pintype "output"))
      (node (ref "X-SOUTH") (pin "58") (pinfunction "58_58") (pintype "bidirectional"))
    )
    (net (code "174") (name "S14_P") (class "Default")
      (node (ref "SENSOR") (pin "C20") (pinfunction "OUT25_P_C20") (pintype "output"))
      (node (ref "X-SOUTH") (pin "56") (pinfunction "56_56") (pintype "bidirectional"))
    )
    (net (code "175") (name "S15_N") (class "Default")
      (node (ref "SENSOR") (pin "B18") (pinfunction "OUT22_N_B18") (pintype "output"))
      (node (ref "X-SOUTH") (pin "59") (pinfunction "59_59") (pintype "bidirectional"))
    )
    (net (code "176") (name "S15_P") (class "Default")
      (node (ref "SENSOR") (pin "B19") (pinfunction "OUT22_P_B19") (pintype "output"))
      (node (ref "X-SOUTH") (pin "57") (pinfunction "57_57") (pintype "bidirectional"))
    )
    (net (code "177") (name "S16_N") (class "Default")
      (node (ref "SENSOR") (pin "C17") (pinfunction "OUT21_N_C17") (pintype "output"))
      (node (ref "X-SOUTH") (pin "64") (pinfunction "64_64") (pintype "bidirectional"))
    )
    (net (code "178") (name "S16_P") (class "Default")
      (node (ref "SENSOR") (pin "C18") (pinfunction "OUT21_P_C18") (pintype "output"))
      (node (ref "X-SOUTH") (pin "62") (pinfunction "62_62") (pintype "bidirectional"))
    )
    (net (code "179") (name "S17_N") (class "Default")
      (node (ref "SENSOR") (pin "A17") (pinfunction "OUT19_N_A17") (pintype "output"))
      (node (ref "X-SOUTH") (pin "65") (pinfunction "65_65") (pintype "bidirectional"))
    )
    (net (code "180") (name "S17_P") (class "Default")
      (node (ref "SENSOR") (pin "A18") (pinfunction "OUT19_P_A18") (pintype "output"))
      (node (ref "X-SOUTH") (pin "63") (pinfunction "63_63") (pintype "bidirectional"))
    )
    (net (code "181") (name "S18_N") (class "Default")
      (node (ref "SENSOR") (pin "D17") (pinfunction "OUT20_N_D17") (pintype "output"))
      (node (ref "X-SOUTH") (pin "70") (pinfunction "70_70") (pintype "bidirectional"))
    )
    (net (code "182") (name "S18_P") (class "Default")
      (node (ref "SENSOR") (pin "D18") (pinfunction "OUT20_P_D18") (pintype "output"))
      (node (ref "X-SOUTH") (pin "68") (pinfunction "68_68") (pintype "bidirectional"))
    )
    (net (code "183") (name "S19_N") (class "Default")
      (node (ref "SENSOR") (pin "B16") (pinfunction "OUT18_N_B16") (pintype "output"))
      (node (ref "X-SOUTH") (pin "71") (pinfunction "71_71") (pintype "bidirectional"))
    )
    (net (code "184") (name "S19_P") (class "Default")
      (node (ref "SENSOR") (pin "B17") (pinfunction "OUT18_P_B17") (pintype "output"))
      (node (ref "X-SOUTH") (pin "69") (pinfunction "69_69") (pintype "bidirectional"))
    )
    (net (code "185") (name "S20_N") (class "Default")
      (node (ref "SENSOR") (pin "D15") (pinfunction "OUT17_N_D15") (pintype "output"))
      (node (ref "X-SOUTH") (pin "76") (pinfunction "76_76") (pintype "bidirectional"))
    )
    (net (code "186") (name "S20_P") (class "Default")
      (node (ref "SENSOR") (pin "D16") (pinfunction "OUT17_P_D16") (pintype "output"))
      (node (ref "X-SOUTH") (pin "74") (pinfunction "74_74") (pintype "bidirectional"))
    )
    (net (code "187") (name "S21_N") (class "Default")
      (node (ref "SENSOR") (pin "B14") (pinfunction "OUT16_N_B14") (pintype "output"))
      (node (ref "X-SOUTH") (pin "77") (pinfunction "77_77") (pintype "bidirectional"))
    )
    (net (code "188") (name "S21_P") (class "Default")
      (node (ref "SENSOR") (pin "B15") (pinfunction "OUT16_P_B15") (pintype "output"))
      (node (ref "X-SOUTH") (pin "75") (pinfunction "75_75") (pintype "bidirectional"))
    )
    (net (code "189") (name "S22_N") (class "Default")
      (node (ref "SENSOR") (pin "D13") (pinfunction "OUT15_N_D13") (pintype "output"))
      (node (ref "X-SOUTH") (pin "82") (pinfunction "82_82") (pintype "bidirectional"))
    )
    (net (code "190") (name "S22_P") (class "Default")
      (node (ref "SENSOR") (pin "D14") (pinfunction "OUT15_P_D14") (pintype "output"))
      (node (ref "X-SOUTH") (pin "80") (pinfunction "80_80") (pintype "bidirectional"))
    )
    (net (code "191") (name "S23_N") (class "Default")
      (node (ref "SENSOR") (pin "A13") (pinfunction "OUT13_N_A13") (pintype "output"))
      (node (ref "X-SOUTH") (pin "83") (pinfunction "83_83") (pintype "bidirectional"))
    )
    (net (code "192") (name "S23_P") (class "Default")
      (node (ref "SENSOR") (pin "A14") (pinfunction "OUT13_P_A14") (pintype "output"))
      (node (ref "X-SOUTH") (pin "81") (pinfunction "81_81") (pintype "bidirectional"))
    )
    (net (code "193") (name "S24_N") (class "Default")
      (node (ref "SENSOR") (pin "C13") (pinfunction "OUT14_N_C13") (pintype "output"))
      (node (ref "X-SOUTH") (pin "88") (pinfunction "88_88") (pintype "bidirectional"))
    )
    (net (code "194") (name "S24_P") (class "Default")
      (node (ref "SENSOR") (pin "C14") (pinfunction "OUT14_P_C14") (pintype "output"))
      (node (ref "X-SOUTH") (pin "86") (pinfunction "86_86") (pintype "bidirectional"))
    )
    (net (code "195") (name "S25_N") (class "Default")
      (node (ref "SENSOR") (pin "B12") (pinfunction "OUT12_N_B12") (pintype "output"))
      (node (ref "X-SOUTH") (pin "89") (pinfunction "89_89") (pintype "bidirectional"))
    )
    (net (code "196") (name "S25_P") (class "Default")
      (node (ref "SENSOR") (pin "B13") (pinfunction "OUT12_P_B13") (pintype "output"))
      (node (ref "X-SOUTH") (pin "87") (pinfunction "87_87") (pintype "bidirectional"))
    )
    (net (code "197") (name "S26_N") (class "Default")
      (node (ref "SENSOR") (pin "D11") (pinfunction "OUT10_N_D11") (pintype "output"))
      (node (ref "X-SOUTH") (pin "94") (pinfunction "94_94") (pintype "bidirectional"))
    )
    (net (code "198") (name "S26_P") (class "Default")
      (node (ref "SENSOR") (pin "D12") (pinfunction "OUT10_P_D12") (pintype "output"))
      (node (ref "X-SOUTH") (pin "92") (pinfunction "92_92") (pintype "bidirectional"))
    )
    (net (code "199") (name "S27_N") (class "Default")
      (node (ref "SENSOR") (pin "A11") (pinfunction "OUT9_N_A11") (pintype "output"))
      (node (ref "X-SOUTH") (pin "95") (pinfunction "95_95") (pintype "bidirectional"))
    )
    (net (code "200") (name "S27_P") (class "Default")
      (node (ref "SENSOR") (pin "A12") (pinfunction "OUT9_P_A12") (pintype "output"))
      (node (ref "X-SOUTH") (pin "93") (pinfunction "93_93") (pintype "bidirectional"))
    )
    (net (code "201") (name "S28_N") (class "Default")
      (node (ref "SENSOR") (pin "C11") (pinfunction "OUT11_N_C11") (pintype "output"))
      (node (ref "X-SOUTH") (pin "100") (pinfunction "100_100") (pintype "bidirectional"))
    )
    (net (code "202") (name "S28_P") (class "Default")
      (node (ref "SENSOR") (pin "C12") (pinfunction "OUT11_P_C12") (pintype "output"))
      (node (ref "X-SOUTH") (pin "98") (pinfunction "98_98") (pintype "bidirectional"))
    )
    (net (code "203") (name "S29_N") (class "Default")
      (node (ref "SENSOR") (pin "B10") (pinfunction "OUT8_N_B10") (pintype "output"))
      (node (ref "X-SOUTH") (pin "101") (pinfunction "101_101") (pintype "bidirectional"))
    )
    (net (code "204") (name "S29_P") (class "Default")
      (node (ref "SENSOR") (pin "B11") (pinfunction "OUT8_P_B11") (pintype "output"))
      (node (ref "X-SOUTH") (pin "99") (pinfunction "99_99") (pintype "bidirectional"))
    )
    (net (code "205") (name "S30_N") (class "Default")
      (node (ref "SENSOR") (pin "C9") (pinfunction "OUT7_N_C9") (pintype "output"))
      (node (ref "X-SOUTH") (pin "106") (pinfunction "106_106") (pintype "bidirectional"))
    )
    (net (code "206") (name "S30_P") (class "Default")
      (node (ref "SENSOR") (pin "C10") (pinfunction "OUT7_P_C10") (pintype "output"))
      (node (ref "X-SOUTH") (pin "104") (pinfunction "104_104") (pintype "bidirectional"))
    )
    (net (code "207") (name "S31_N") (class "Default")
      (node (ref "SENSOR") (pin "B8") (pinfunction "OUT5_N_B8") (pintype "output"))
      (node (ref "X-SOUTH") (pin "107") (pinfunction "107_107") (pintype "bidirectional"))
    )
    (net (code "208") (name "S31_P") (class "Default")
      (node (ref "SENSOR") (pin "B9") (pinfunction "OUT5_P_B9") (pintype "output"))
      (node (ref "X-SOUTH") (pin "105") (pinfunction "105_105") (pintype "bidirectional"))
    )
    (net (code "209") (name "S32_N") (class "Default")
      (node (ref "SENSOR") (pin "D9") (pinfunction "OUT6_N_D9") (pintype "output"))
      (node (ref "X-SOUTH") (pin "112") (pinfunction "112_112") (pintype "bidirectional"))
    )
    (net (code "210") (name "S32_P") (class "Default")
      (node (ref "SENSOR") (pin "D10") (pinfunction "OUT6_P_D10") (pintype "output"))
      (node (ref "X-SOUTH") (pin "110") (pinfunction "110_110") (pintype "bidirectional"))
    )
    (net (code "211") (name "S33_N") (class "Default")
      (node (ref "SENSOR") (pin "A7") (pinfunction "OUT2_N_A7") (pintype "output"))
      (node (ref "X-SOUTH") (pin "113") (pinfunction "113_113") (pintype "bidirectional"))
    )
    (net (code "212") (name "S33_P") (class "Default")
      (node (ref "SENSOR") (pin "A8") (pinfunction "OUT2_P_A8") (pintype "output"))
      (node (ref "X-SOUTH") (pin "111") (pinfunction "111_111") (pintype "bidirectional"))
    )
    (net (code "213") (name "S34_N") (class "Default")
      (node (ref "SENSOR") (pin "C7") (pinfunction "OUT4_N_C7") (pintype "output"))
      (node (ref "X-SOUTH") (pin "118") (pinfunction "118_118") (pintype "bidirectional"))
    )
    (net (code "214") (name "S34_P") (class "Default")
      (node (ref "SENSOR") (pin "C8") (pinfunction "OUT4_P_C8") (pintype "output"))
      (node (ref "X-SOUTH") (pin "116") (pinfunction "116_116") (pintype "bidirectional"))
    )
    (net (code "215") (name "S35_N") (class "Default")
      (node (ref "SENSOR") (pin "B6") (pinfunction "OUT1_N_B6") (pintype "output"))
      (node (ref "X-SOUTH") (pin "119") (pinfunction "119_119") (pintype "bidirectional"))
    )
    (net (code "216") (name "S35_P") (class "Default")
      (node (ref "SENSOR") (pin "B7") (pinfunction "OUT1_P_B7") (pintype "output"))
      (node (ref "X-SOUTH") (pin "117") (pinfunction "117_117") (pintype "bidirectional"))
    )
    (net (code "217") (name "S36_N") (class "Default")
      (node (ref "SENSOR") (pin "D7") (pinfunction "OUT3_N_D7") (pintype "output"))
      (node (ref "X-SOUTH") (pin "124") (pinfunction "124_124") (pintype "bidirectional"))
    )
    (net (code "218") (name "S36_P") (class "Default")
      (node (ref "SENSOR") (pin "D8") (pinfunction "OUT3_P_D8") (pintype "output"))
      (node (ref "X-SOUTH") (pin "122") (pinfunction "122_122") (pintype "bidirectional"))
    )
    (net (code "219") (name "S37_N") (class "Default")
      (node (ref "SENSOR") (pin "A5") (pinfunction "OUTCTR_N_A5") (pintype "output"))
      (node (ref "X-SOUTH") (pin "125") (pinfunction "125_125") (pintype "bidirectional"))
    )
    (net (code "220") (name "S37_P") (class "Default")
      (node (ref "SENSOR") (pin "A6") (pinfunction "OUTCTR_P_A6") (pintype "output"))
      (node (ref "X-SOUTH") (pin "123") (pinfunction "123_123") (pintype "bidirectional"))
    )
    (net (code "221") (name "S38_N") (class "Default")
      (node (ref "X-SOUTH") (pin "130") (pinfunction "130_130") (pintype "bidirectional"))
    )
    (net (code "222") (name "S38_P") (class "Default")
      (node (ref "X-SOUTH") (pin "128") (pinfunction "128_128") (pintype "bidirectional"))
    )
    (net (code "223") (name "S39_N") (class "Default")
      (node (ref "U3") (pin "6") (pinfunction "EN_6") (pintype "input"))
      (node (ref "X-SOUTH") (pin "131") (pinfunction "131_131") (pintype "bidirectional"))
    )
    (net (code "224") (name "S39_P") (class "Default")
      (node (ref "X-SOUTH") (pin "129") (pinfunction "129_129") (pintype "bidirectional"))
    )
    (net (code "225") (name "SPI_CLK") (class "Default")
      (node (ref "SENSOR") (pin "H29") (pinfunction "SPI_CLK_H29") (pintype "input"))
      (node (ref "U4") (pin "9") (pinfunction "B4_9") (pintype "bidirectional"))
    )
    (net (code "226") (name "SPI_EN") (class "Default")
      (node (ref "SENSOR") (pin "F28") (pinfunction "SPI_EN_F28") (pintype "input"))
      (node (ref "U4") (pin "12") (pinfunction "B1_12") (pintype "bidirectional"))
    )
    (net (code "227") (name "SPI_IN") (class "Default")
      (node (ref "SENSOR") (pin "E28") (pinfunction "SPI_IN_E28") (pintype "input"))
      (node (ref "U4") (pin "10") (pinfunction "B3_10") (pintype "bidirectional"))
    )
    (net (code "228") (name "SPI_OUT") (class "Default")
      (node (ref "SENSOR") (pin "G28") (pinfunction "SPI_OUT_G28") (pintype "output"))
      (node (ref "U4") (pin "11") (pinfunction "B2_11") (pintype "bidirectional"))
    )
    (net (code "229") (name "SYS_RES_N") (class "Default")
      (node (ref "SENSOR") (pin "F30") (pinfunction "SYS_RES_N_F30") (pintype "input"))
      (node (ref "U5") (pin "10") (pinfunction "B3_10") (pintype "bidirectional"))
    )
    (net (code "230") (name "S_CHK_EN") (class "Default")
      (node (ref "X-SOUTH") (pin "8") (pinfunction "8_8") (pintype "bidirectional"))
    )
    (net (code "231") (name "S_CHK_V") (class "Default")
      (node (ref "C5") (pin "1") (pinfunction "1_1") (pintype "passive"))
      (node (ref "C6") (pin "1") (pinfunction "1_1") (pintype "passive"))
      (node (ref "C7") (pin "1") (pinfunction "1_1") (pintype "passive"))
      (node (ref "R20") (pin "1") (pinfunction "1_1") (pintype "passive"))
      (node (ref "TP3") (pin "TP") (pinfunction "TP_TP") (pintype "input"))
      (node (ref "USE") (pin "8") (pinfunction "VDD_8") (pintype "power_in"))
      (node (ref "USS") (pin "8") (pinfunction "VDD_8") (pintype "power_in"))
      (node (ref "USW") (pin "8") (pinfunction "VDD_8") (pintype "power_in"))
      (node (ref "X-SOUTH") (pin "10") (pinfunction "10_10") (pintype "bidirectional"))
    )
    (net (code "232") (name "S_I2C_EN") (class "Default")
      (node (ref "X-SOUTH") (pin "137") (pinfunction "137_137") (pintype "bidirectional"))
    )
    (net (code "233") (name "S_I2C_V") (class "Default")
      (node (ref "U7") (pin "8") (pinfunction "VCC_8") (pintype "power_in"))
      (node (ref "X-SOUTH") (pin "135") (pinfunction "135_135") (pintype "bidirectional"))
    )
    (net (code "234") (name "S_REF") (class "Default")
      (node (ref "R20") (pin "2") (pinfunction "2_2") (pintype "passive"))
      (node (ref "TP4") (pin "TP") (pinfunction "TP_TP") (pintype "input"))
      (node (ref "U2") (pin "1") (pinfunction "CATHODE_1") (pintype "output"))
      (node (ref "U2") (pin "3") (pinfunction "REF_3") (pintype "input"))
      (node (ref "USE") (pin "2") (pinfunction "VINA-_2") (pintype "input"))
      (node (ref "USE") (pin "5") (pinfunction "VINB+_5") (pintype "input"))
      (node (ref "USS") (pin "2") (pinfunction "VINA-_2") (pintype "input"))
      (node (ref "USS") (pin "5") (pinfunction "VINB+_5") (pintype "input"))
      (node (ref "USW") (pin "2") (pinfunction "VINA-_2") (pintype "input"))
      (node (ref "USW") (pin "5") (pinfunction "VINB+_5") (pintype "input"))
    )
    (net (code "235") (name "S_SCK") (class "Default")
      (node (ref "X-SOUTH") (pin "144") (pinfunction "144_144") (pintype "bidirectional"))
    )
    (net (code "236") (name "S_SCL") (class "Default")
      (node (ref "U7") (pin "2") (pinfunction "SCL_2") (pintype "input"))
      (node (ref "X-SOUTH") (pin "143") (pinfunction "143_143") (pintype "bidirectional"))
    )
    (net (code "237") (name "S_SDA") (class "Default")
      (node (ref "U7") (pin "1") (pinfunction "SDA_1") (pintype "bidirectional"))
      (node (ref "X-SOUTH") (pin "141") (pinfunction "141_141") (pintype "bidirectional"))
    )
    (net (code "238") (name "S_SDI") (class "Default")
      (node (ref "X-SOUTH") (pin "140") (pinfunction "140_140") (pintype "bidirectional"))
    )
    (net (code "239") (name "S_SDO") (class "Default")
      (node (ref "X-SOUTH") (pin "142") (pinfunction "142_142") (pintype "bidirectional"))
    )
    (net (code "240") (name "S_SPI_EN") (class "Default")
      (node (ref "X-SOUTH") (pin "136") (pinfunction "136_136") (pintype "bidirectional"))
    )
    (net (code "241") (name "S_SPI_V") (class "Default")
      (node (ref "X-SOUTH") (pin "134") (pinfunction "134_134") (pintype "bidirectional"))
    )
    (net (code "242") (name "S_VE") (class "Default")
      (node (ref "X-SOUTH") (pin "13") (pinfunction "13_13") (pintype "bidirectional"))
      (node (ref "X-SOUTH") (pin "19") (pinfunction "19_19") (pintype "bidirectional"))
      (node (ref "X-SOUTH") (pin "25") (pinfunction "25_25") (pintype "bidirectional"))
      (node (ref "X-SOUTH") (pin "31") (pinfunction "31_31") (pintype "bidirectional"))
      (node (ref "X-SOUTH") (pin "37") (pinfunction "37_37") (pintype "bidirectional"))
    )
    (net (code "243") (name "S_VE_CV") (class "Default")
      (node (ref "C11") (pin "1") (pinfunction "1_1") (pintype "passive"))
      (node (ref "R10") (pin "1") (pinfunction "1_1") (pintype "passive"))
      (node (ref "X-SOUTH") (pin "2") (pinfunction "2_2") (pintype "bidirectional"))
    )
    (net (code "244") (name "S_VE_OV") (class "Default")
      (node (ref "USE") (pin "7") (pinfunction "OUTB_7") (pintype "output"))
      (node (ref "X-SOUTH") (pin "1") (pinfunction "1_1") (pintype "bidirectional"))
    )
    (net (code "245") (name "S_VE_UV") (class "Default")
      (node (ref "USE") (pin "1") (pinfunction "OUTA_1") (pintype "output"))
      (node (ref "X-SOUTH") (pin "7") (pinfunction "7_7") (pintype "bidirectional"))
    )
    (net (code "246") (name "S_VS") (class "Default")
      (node (ref "C45") (pin "1") (pinfunction "1_1") (pintype "passive"))
      (node (ref "C46") (pin "1") (pinfunction "1_1") (pintype "passive"))
      (node (ref "C47") (pin "1") (pinfunction "1_1") (pintype "passive"))
      (node (ref "C48") (pin "1") (pinfunction "1_1") (pintype "passive"))
      (node (ref "C49") (pin "1") (pinfunction "1_1") (pintype "passive"))
      (node (ref "C72") (pin "1") (pinfunction "1_1") (pintype "passive"))
      (node (ref "C73") (pin "1") (pinfunction "1_1") (pintype "passive"))
      (node (ref "C74") (pin "1") (pinfunction "1_1") (pintype "passive"))
      (node (ref "C81") (pin "1") (pinfunction "1_1") (pintype "passive"))
      (node (ref "C82") (pin "1") (pinfunction "1_1") (pintype "passive"))
      (node (ref "C83") (pin "1") (pinfunction "1_1") (pintype "passive"))
      (node (ref "SENSOR") (pin "A30") (pinfunction "VDD_PIX_A30") (pintype "power_in"))
      (node (ref "SENSOR") (pin "D28") (pinfunction "VDD_PIX_D28") (pintype "power_in"))
      (node (ref "SENSOR") (pin "D30") (pinfunction "VDD_PIX_D30") (pintype "power_in"))
      (node (ref "SENSOR") (pin "G1") (pinfunction "VDD_PIX_G1") (pintype "power_in"))
      (node (ref "SENSOR") (pin "H28") (pinfunction "VDD_PIX_H28") (pintype "power_in"))
      (node (ref "TP6") (pin "TP") (pinfunction "TP_TP") (pintype "input"))
      (node (ref "X-SOUTH") (pin "49") (pinfunction "49_49") (pintype "bidirectional"))
      (node (ref "X-SOUTH") (pin "55") (pinfunction "55_55") (pintype "bidirectional"))
      (node (ref "X-SOUTH") (pin "61") (pinfunction "61_61") (pintype "bidirectional"))
      (node (ref "X-SOUTH") (pin "67") (pinfunction "67_67") (pintype "bidirectional"))
      (node (ref "X-SOUTH") (pin "73") (pinfunction "73_73") (pintype "bidirectional"))
      (node (ref "X-SOUTH") (pin "79") (pinfunction "79_79") (pintype "bidirectional"))
      (node (ref "X-SOUTH") (pin "85") (pinfunction "85_85") (pintype "bidirectional"))
      (node (ref "X-SOUTH") (pin "91") (pinfunction "91_91") (pintype "bidirectional"))
      (node (ref "X-SOUTH") (pin "97") (pinfunction "97_97") (pintype "bidirectional"))
    )
    (net (code "247") (name "S_VS_CV") (class "Default")
      (node (ref "C12") (pin "1") (pinfunction "1_1") (pintype "passive"))
      (node (ref "R13") (pin "1") (pinfunction "1_1") (pintype "passive"))
      (node (ref "X-SOUTH") (pin "4") (pinfunction "4_4") (pintype "bidirectional"))
    )
    (net (code "248") (name "S_VS_OV") (class "Default")
      (node (ref "USS") (pin "7") (pinfunction "OUTB_7") (pintype "output"))
      (node (ref "X-SOUTH") (pin "3") (pinfunction "3_3") (pintype "bidirectional"))
    )
    (net (code "249") (name "S_VS_UV") (class "Default")
      (node (ref "USS") (pin "1") (pinfunction "OUTA_1") (pintype "output"))
      (node (ref "X-SOUTH") (pin "9") (pinfunction "9_9") (pintype "bidirectional"))
    )
    (net (code "250") (name "S_VW") (class "Default")
      (node (ref "C90") (pin "1") (pinfunction "1_1") (pintype "passive"))
      (node (ref "U3") (pin "1") (pinfunction "BIAS_1") (pintype "power_in"))
      (node (ref "U3") (pin "3") (pinfunction "IN_3") (pintype "power_in"))
      (node (ref "X-SOUTH") (pin "109") (pinfunction "109_109") (pintype "bidirectional"))
      (node (ref "X-SOUTH") (pin "115") (pinfunction "115_115") (pintype "bidirectional"))
      (node (ref "X-SOUTH") (pin "121") (pinfunction "121_121") (pintype "bidirectional"))
      (node (ref "X-SOUTH") (pin "127") (pinfunction "127_127") (pintype "bidirectional"))
      (node (ref "X-SOUTH") (pin "133") (pinfunction "133_133") (pintype "bidirectional"))
    )
    (net (code "251") (name "S_VW_CV") (class "Default")
      (node (ref "C13") (pin "1") (pinfunction "1_1") (pintype "passive"))
      (node (ref "R16") (pin "1") (pinfunction "1_1") (pintype "passive"))
      (node (ref "X-SOUTH") (pin "6") (pinfunction "6_6") (pintype "bidirectional"))
    )
    (net (code "252") (name "S_VW_OV") (class "Default")
      (node (ref "USW") (pin "7") (pinfunction "OUTB_7") (pintype "output"))
      (node (ref "X-SOUTH") (pin "5") (pinfunction "5_5") (pintype "bidirectional"))
    )
    (net (code "253") (name "S_VW_UV") (class "Default")
      (node (ref "USW") (pin "1") (pinfunction "OUTA_1") (pintype "output"))
      (node (ref "X-SOUTH") (pin "11") (pinfunction "11_11") (pintype "bidirectional"))
    )
    (net (code "254") (name "TDIG1") (class "Default")
      (node (ref "SENSOR") (pin "G27") (pinfunction "TDIG1_G27") (pintype "output"))
      (node (ref "U5") (pin "9") (pinfunction "B4_9") (pintype "bidirectional"))
    )
    (net (code "255") (name "TDIG2") (class "Default")
      (node (ref "SENSOR") (pin "G26") (pinfunction "TDIG2_G26") (pintype "output"))
      (node (ref "U6") (pin "11") (pinfunction "B2_11") (pintype "bidirectional"))
    )
    (net (code "256") (name "T_EXP1") (class "Default")
      (node (ref "SENSOR") (pin "H30") (pinfunction "T_EXP1_H30") (pintype "input"))
      (node (ref "U5") (pin "12") (pinfunction "B1_12") (pintype "bidirectional"))
    )
    (net (code "257") (name "T_EXP2") (class "Default")
      (node (ref "SENSOR") (pin "E29") (pinfunction "T_EXP2_E29") (pintype "input"))
      (node (ref "U6") (pin "10") (pinfunction "B3_10") (pintype "bidirectional"))
    )
    (net (code "258") (name "VRAMP1") (class "Default")
      (node (ref "C16") (pin "1") (pinfunction "1_1") (pintype "passive"))
      (node (ref "R23") (pin "1") (pinfunction "1_1") (pintype "passive"))
      (node (ref "SENSOR") (pin "G29") (pinfunction "VRAMP1_G29") (pintype "bidirectional"))
    )
    (net (code "259") (name "VRAMP2") (class "Default")
      (node (ref "C17") (pin "1") (pinfunction "1_1") (pintype "passive"))
      (node (ref "R23") (pin "2") (pinfunction "2_2") (pintype "passive"))
      (node (ref "SENSOR") (pin "F29") (pinfunction "VRAMP2_F29") (pintype "bidirectional"))
    )
    (net (code "260") (name "VTREF") (class "Default")
      (node (ref "C65") (pin "1") (pinfunction "1_1") (pintype "passive"))
      (node (ref "C91") (pin "2") (pinfunction "2_2") (pintype "passive"))
      (node (ref "R21") (pin "2") (pinfunction "2_2") (pintype "passive"))
      (node (ref "R24") (pin "1") (pinfunction "1_1") (pintype "passive"))
      (node (ref "SENSOR") (pin "B2") (pinfunction "VTREF_B2") (pintype "bidirectional"))
      (node (ref "U3") (pin "4") (pinfunction "OUT_4") (pintype "power_in"))
    )
    (net (code "261") (name "VTSIG") (class "Default")
      (node (ref "C66") (pin "1") (pinfunction "1_1") (pintype "passive"))
      (node (ref "R24") (pin "2") (pinfunction "2_2") (pintype "passive"))
      (node (ref "SENSOR") (pin "C2") (pinfunction "VTSIG_C2") (pintype "bidirectional"))
    )
    (net (code "262") (name "unconnected-(U1-NC-Pad2)") (class "Default")
      (node (ref "U1") (pin "2") (pinfunction "NC_2") (pintype "no_connect"))
    )
    (net (code "263") (name "unconnected-(U1-NC-Pad4)") (class "Default")
      (node (ref "U1") (pin "4") (pinfunction "NC_4") (pintype "no_connect"))
    )
    (net (code "264") (name "unconnected-(U1-NC-Pad5)") (class "Default")
      (node (ref "U1") (pin "5") (pinfunction "NC_5") (pintype "no_connect"))
    )
    (net (code "265") (name "unconnected-(U2-NC-Pad2)") (class "Default")
      (node (ref "U2") (pin "2") (pinfunction "NC_2") (pintype "no_connect"))
    )
    (net (code "266") (name "unconnected-(U2-NC-Pad4)") (class "Default")
      (node (ref "U2") (pin "4") (pinfunction "NC_4") (pintype "no_connect"))
    )
    (net (code "267") (name "unconnected-(U2-NC-Pad5)") (class "Default")
      (node (ref "U2") (pin "5") (pinfunction "NC_5") (pintype "no_connect"))
    )
    (net (code "268") (name "unconnected-(U7-OS-Pad3)") (class "Default")
      (node (ref "U7") (pin "3") (pinfunction "OS_3") (pintype "output"))
    )
    (net (code "269") (name "unconnected-(X-NORTH-PadM1)") (class "Default")
      (node (ref "X-NORTH") (pin "M1") (pinfunction "M1_M1") (pintype "bidirectional"))
    )
    (net (code "270") (name "unconnected-(X-NORTH-PadM2)") (class "Default")
      (node (ref "X-NORTH") (pin "M2") (pinfunction "M2_M2") (pintype "bidirectional"))
    )
    (net (code "271") (name "unconnected-(X-SOUTH-PadM1)") (class "Default")
      (node (ref "X-SOUTH") (pin "M1") (pinfunction "M1_M1") (pintype "bidirectional"))
    )
    (net (code "272") (name "unconnected-(X-SOUTH-PadM2)") (class "Default")
      (node (ref "X-SOUTH") (pin "M2") (pinfunction "M2_M2") (pintype "bidirectional"))
    )
  )
)
